# OBCv4_20.net
KiCad netlist of a schematic drawn in EAGLE
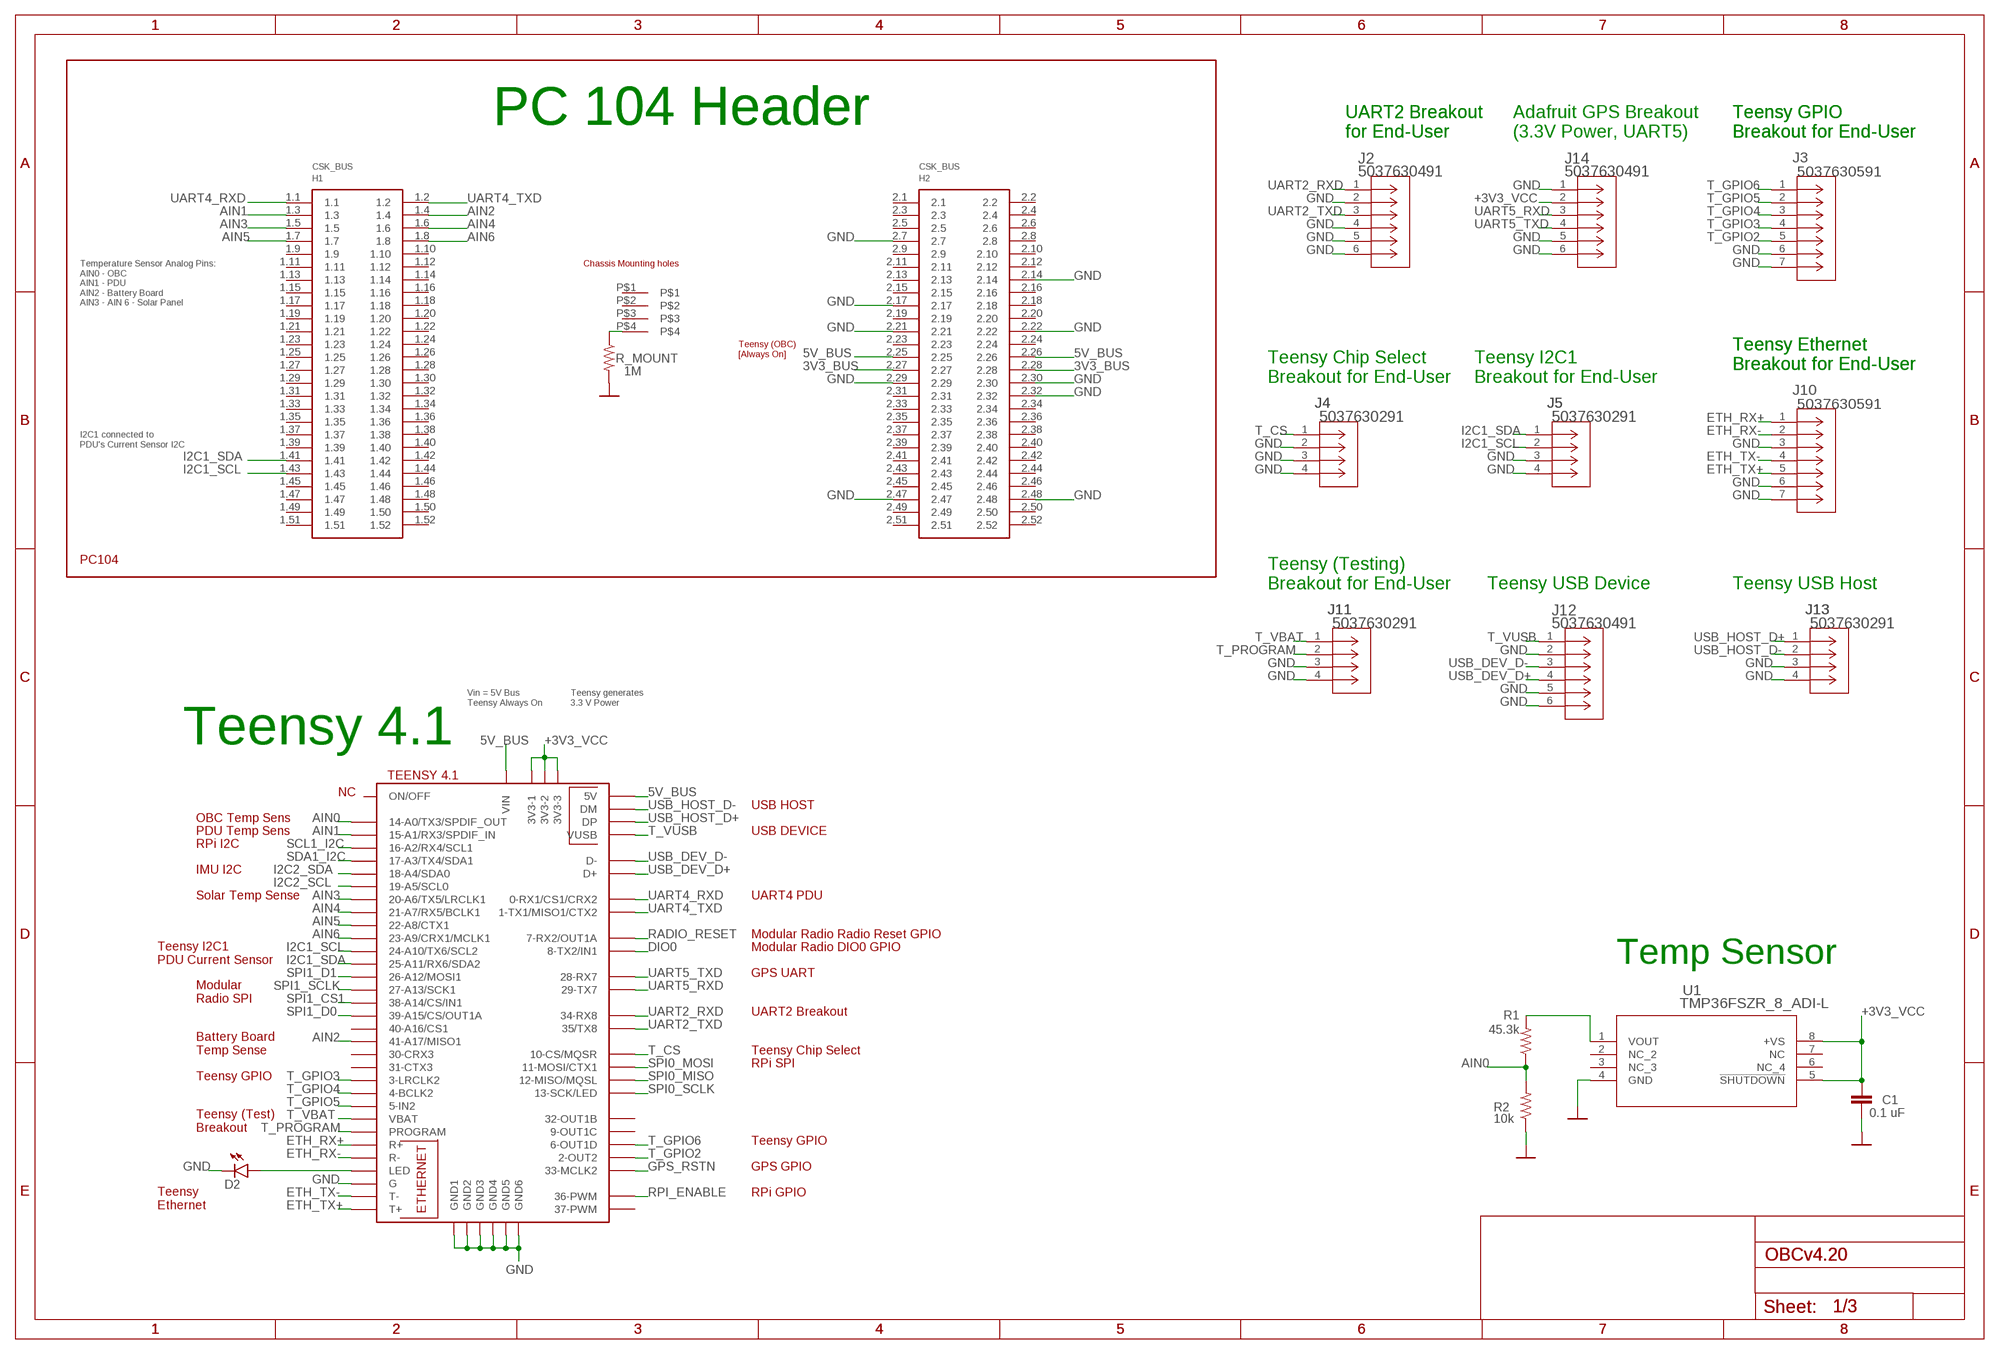
[diagram p0: schematic, sheet 1]
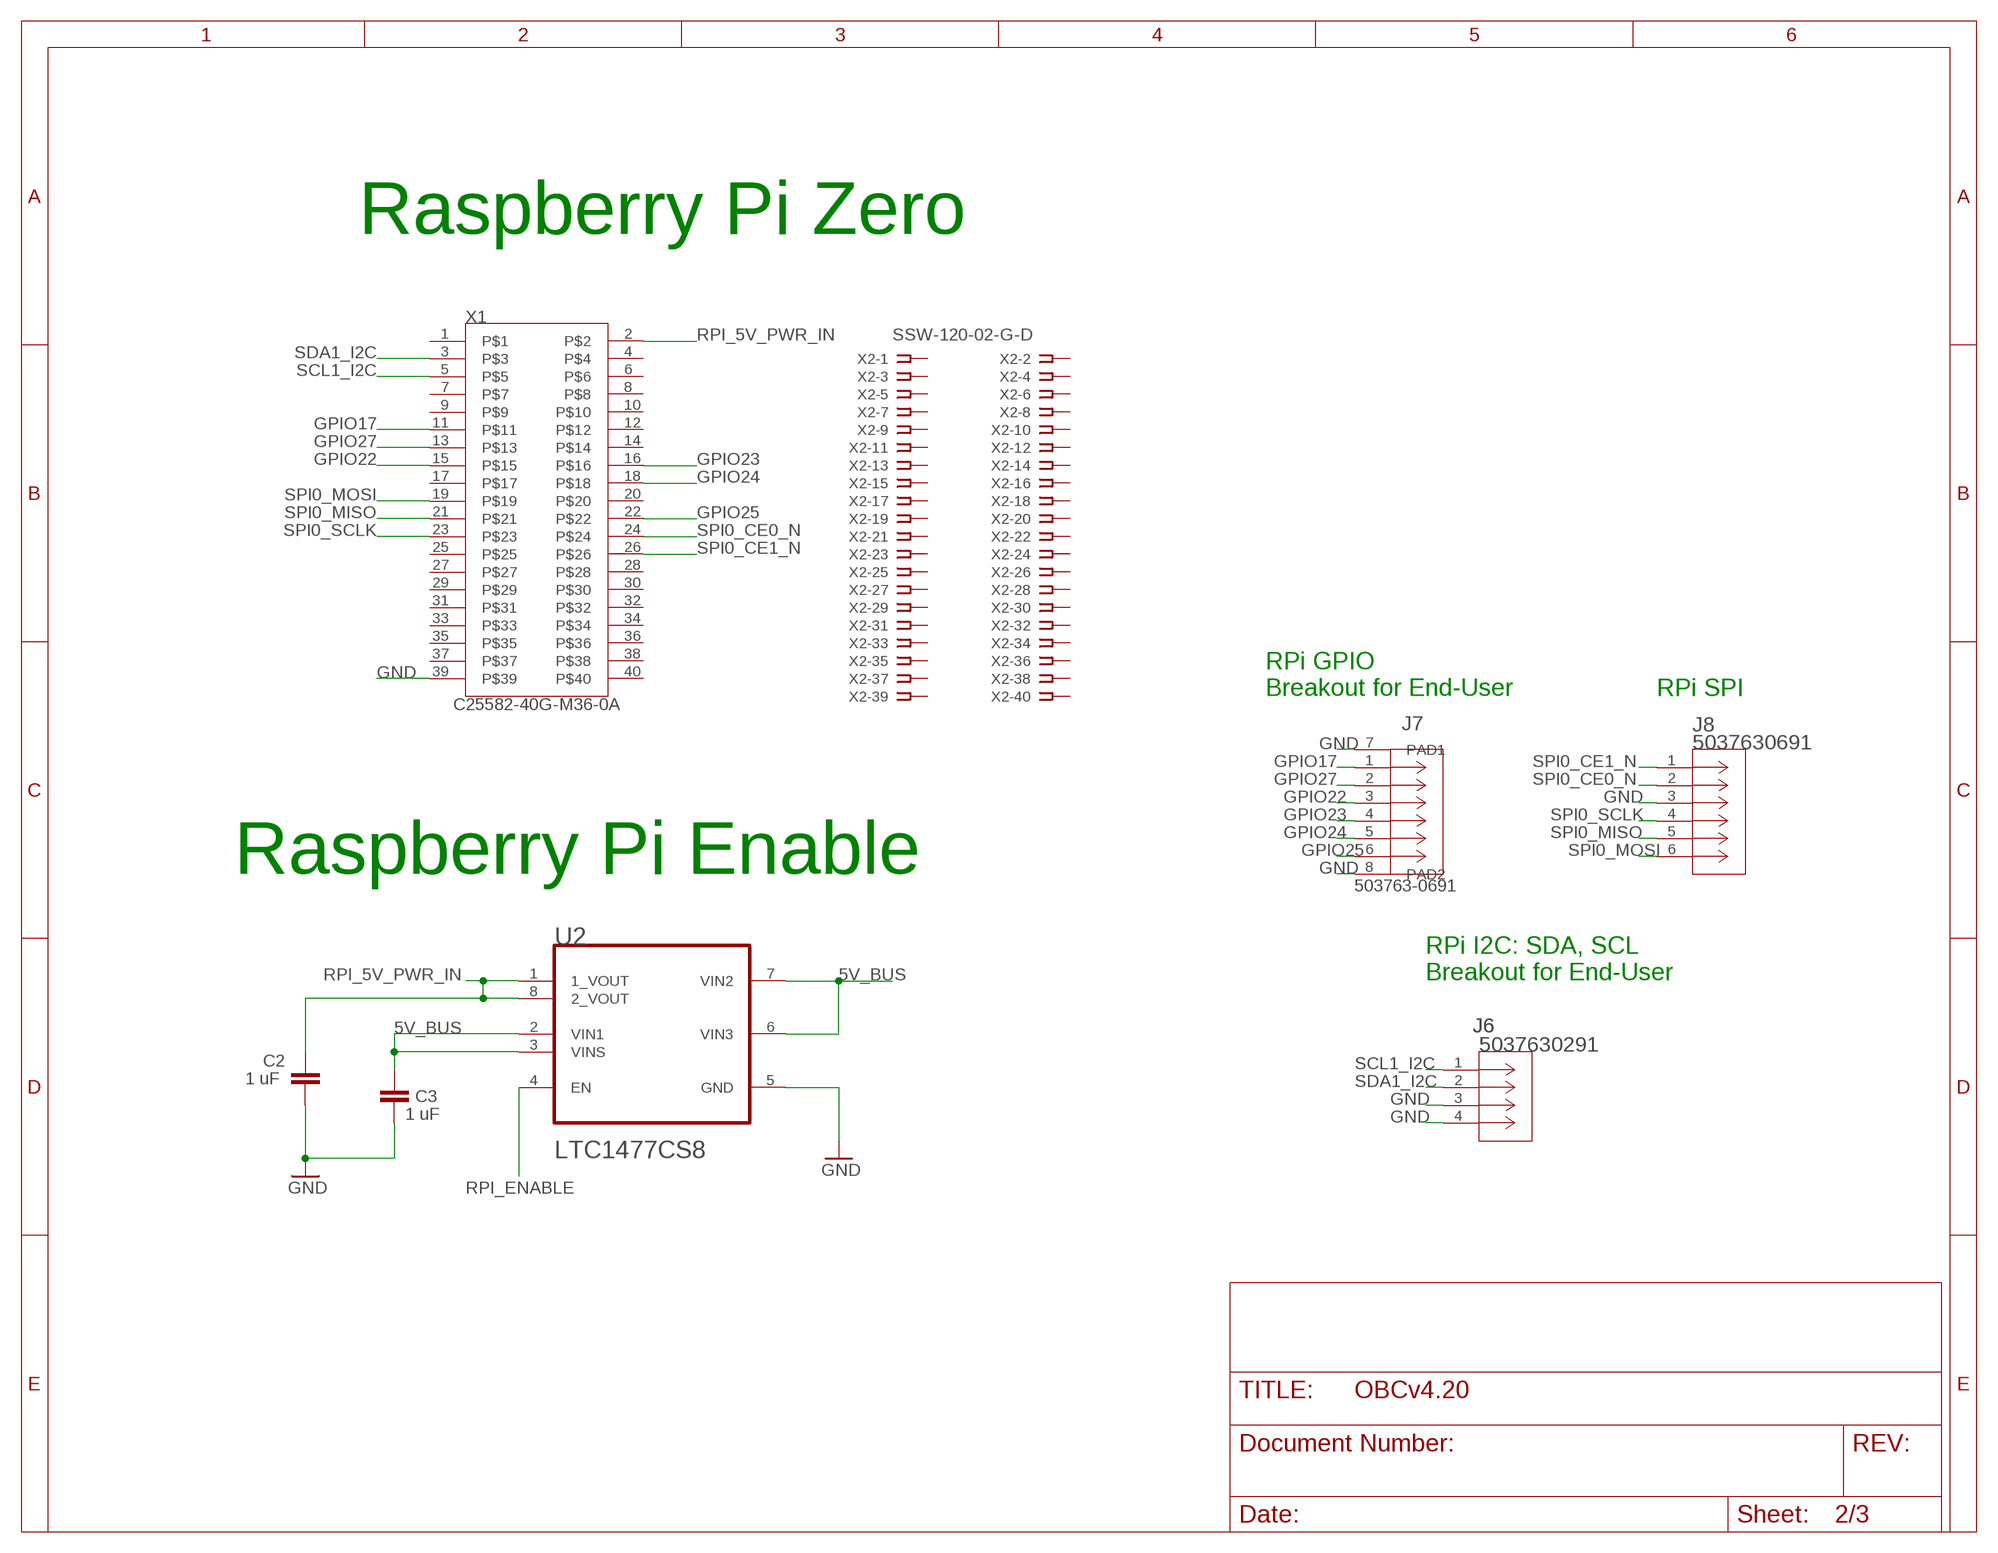
[diagram p1: schematic, sheet 2]
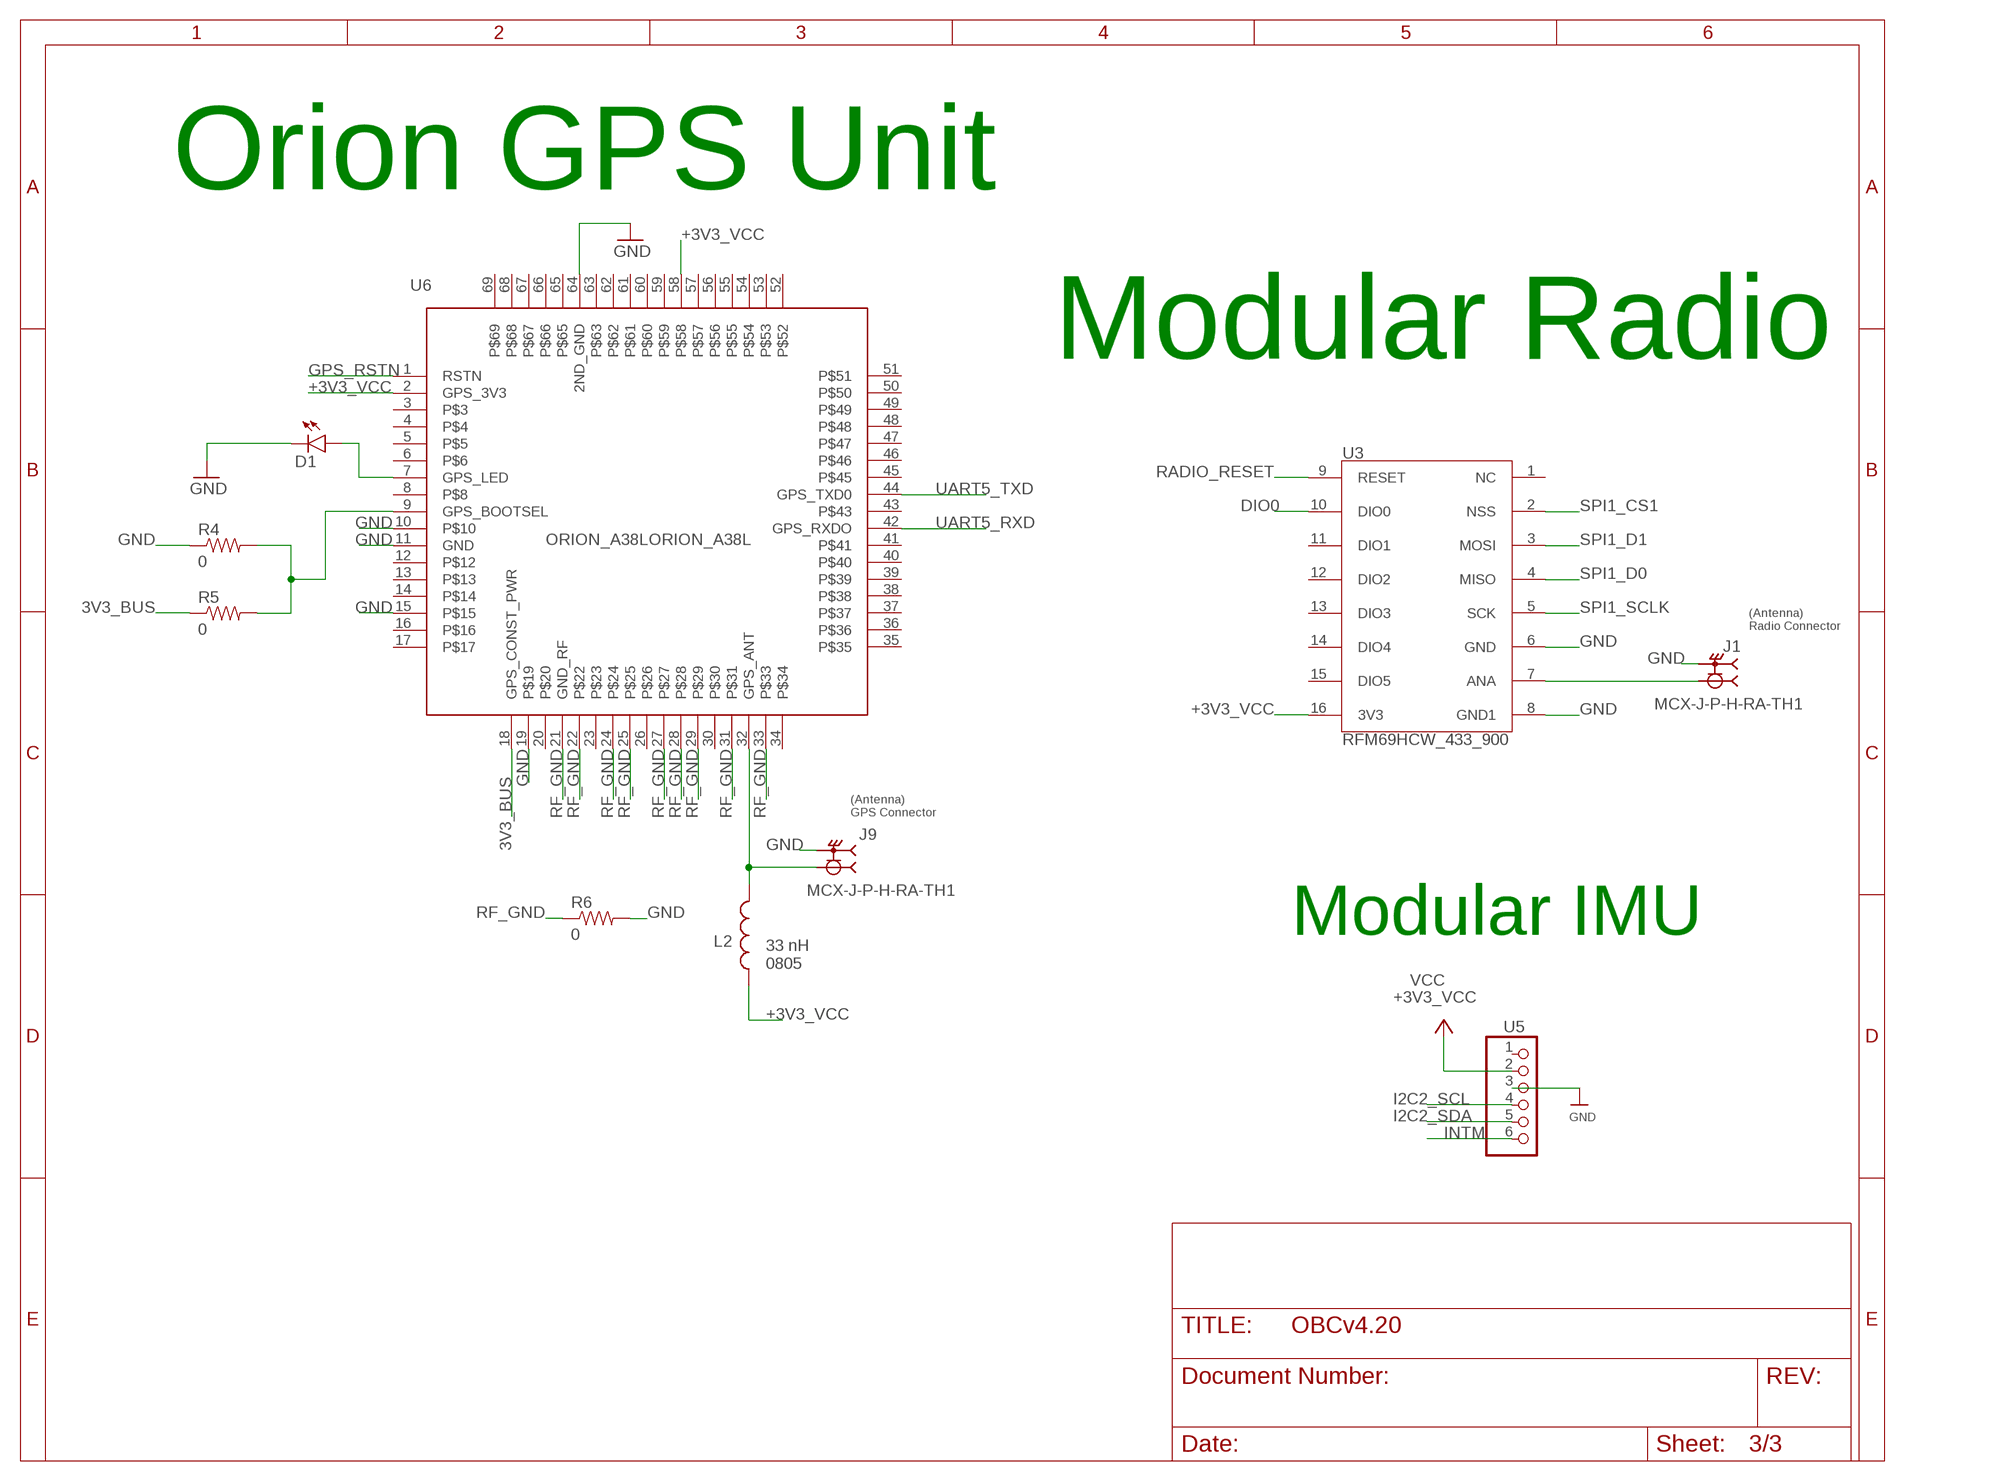
[diagram p2: schematic, sheet 3]

(export (version "E")
  (design (tool "Eeschema 10.0.6"))
  (components
    (comp (ref "C1")
      (value "0.1 uF")
      (footprint "eagle-import:0805")
      (libsource (lib "eagle-import") (part "CAP0805"))
    )
    (comp (ref "D2")
      (value "LEDCHIP-LED0603")
      (footprint "eagle-import:CHIP-LED0603")
      (libsource (lib "eagle-import") (part "LEDCHIP-LED0603"))
    )
    (comp (ref "H1")
      (value "PC104_WCONN")
      (footprint "eagle-import:PC104_WCONN")
      (libsource (lib "eagle-import") (part "PC104_WCONN"))
    )
    (comp (ref "J2")
      (value "5037630491")
      (footprint "eagle-import:CON_5037630491")
      (fields (field (name "COPYRIGHT") "Copyright (C) 2018 Accelerated Designs. All rights reserved"))
      (libsource (lib "eagle-import") (part "5037630491"))
    )
    (comp (ref "J3")
      (value "5037630591")
      (footprint "eagle-import:CON_5037630591")
      (fields (field (name "COPYRIGHT") "Copyright (C) 2021 Ultra Librarian. All rights reserved."))
      (libsource (lib "eagle-import") (part "5037630591"))
    )
    (comp (ref "J4")
      (value "5037630291")
      (footprint "eagle-import:CON_5037630291")
      (fields (field (name "COPYRIGHT") "Copyright (C) 2018 Accelerated Designs. All rights reserved"))
      (libsource (lib "eagle-import") (part "5037630291"))
    )
    (comp (ref "J5")
      (value "5037630291")
      (footprint "eagle-import:CON_5037630291")
      (fields (field (name "COPYRIGHT") "Copyright (C) 2018 Accelerated Designs. All rights reserved"))
      (libsource (lib "eagle-import") (part "5037630291"))
    )
    (comp (ref "J10")
      (value "5037630591")
      (footprint "eagle-import:CON_5037630591")
      (fields (field (name "COPYRIGHT") "Copyright (C) 2021 Ultra Librarian. All rights reserved."))
      (libsource (lib "eagle-import") (part "5037630591"))
    )
    (comp (ref "J11")
      (value "5037630291")
      (footprint "eagle-import:CON_5037630291")
      (fields (field (name "COPYRIGHT") "Copyright (C) 2018 Accelerated Designs. All rights reserved"))
      (libsource (lib "eagle-import") (part "5037630291"))
    )
    (comp (ref "J12")
      (value "5037630491")
      (footprint "eagle-import:CON_5037630491")
      (fields (field (name "COPYRIGHT") "Copyright (C) 2018 Accelerated Designs. All rights reserved"))
      (libsource (lib "eagle-import") (part "5037630491"))
    )
    (comp (ref "J13")
      (value "5037630291")
      (footprint "eagle-import:CON_5037630291")
      (fields (field (name "COPYRIGHT") "Copyright (C) 2018 Accelerated Designs. All rights reserved"))
      (libsource (lib "eagle-import") (part "5037630291"))
    )
    (comp (ref "J14")
      (value "5037630491")
      (footprint "eagle-import:CON_5037630491")
      (fields (field (name "COPYRIGHT") "Copyright (C) 2018 Accelerated Designs. All rights reserved"))
      (libsource (lib "eagle-import") (part "5037630491"))
    )
    (comp (ref "R1")
      (value "45.3k")
      (footprint "eagle-import:0805")
      (libsource (lib "eagle-import") (part "RESISTOR0805-RES"))
    )
    (comp (ref "R2")
      (value "10k")
      (footprint "eagle-import:0805")
      (libsource (lib "eagle-import") (part "RESISTOR0805-RES"))
    )
    (comp (ref "R_MOUNT")
      (value "1M")
      (footprint "eagle-import:0805")
      (libsource (lib "eagle-import") (part "RESISTOR0805-RES"))
    )
    (comp (ref "U$1")
      (value "TEENSY41")
      (footprint "eagle-import:TEENSY41")
      (libsource (lib "eagle-import") (part "TEENSY41"))
    )
    (comp (ref "U1")
      (value "TMP36FSZR_8_ADI-L")
      (footprint "eagle-import:R_8_ADI-L")
      (fields
        (field (name "MANUFACTURER_PART_NUMBER") "TMP36FSZ")
        (field (name "COPYRIGHT") "Copyright (C) 2021 Ultra Librarian. All rights reserved.")
      )
      (libsource (lib "eagle-import") (part "TMP36FSZR_8_ADI-L"))
    )
    (comp (ref "D1")
      (value "LEDCHIP-LED0603")
      (footprint "eagle-import:CHIP-LED0603")
      (libsource (lib "eagle-import") (part "LEDCHIP-LED0603"))
    )
    (comp (ref "J1")
      (value "MCX-J-P-H-RA-TH1")
      (footprint "eagle-import:SAMTEC_MCX-J-P-H-RA-TH1")
      (fields (field (name "DIGI-KEY_PART_NUMBER") "SAM10607-ND") (field (name "MF") "Samtec"))
      (libsource (lib "eagle-import") (part "MCX-J-P-H-RA-TH1"))
    )
    (comp (ref "J9")
      (value "MCX-J-P-H-RA-TH1")
      (footprint "eagle-import:SAMTEC_MCX-J-P-H-RA-TH1")
      (fields (field (name "DIGI-KEY_PART_NUMBER") "SAM10607-ND") (field (name "MF") "Samtec"))
      (libsource (lib "eagle-import") (part "MCX-J-P-H-RA-TH1"))
    )
    (comp (ref "L2")
      (value "AIMC-0805-2N2S-T")
      (footprint "eagle-import:INDC2012X105N")
      (fields (field (name "DIGI-KEY_PART_NUMBER") "535-11562-1-ND") (field (name "MF") "Abracon"))
      (libsource (lib "eagle-import") (part "AIMC-0805-2N2S-T"))
    )
    (comp (ref "R4")
      (value "0")
      (footprint "eagle-import:0805")
      (libsource (lib "eagle-import") (part "RESISTOR0805-RES"))
    )
    (comp (ref "R5")
      (value "0")
      (footprint "eagle-import:0805")
      (libsource (lib "eagle-import") (part "RESISTOR0805-RES"))
    )
    (comp (ref "R6")
      (value "0")
      (footprint "eagle-import:0805")
      (libsource (lib "eagle-import") (part "RESISTOR0805-RES"))
    )
    (comp (ref "U3")
      (value "RFM69HCW_433_900")
      (footprint "eagle-import:RFM69HCW_433")
      (libsource (lib "eagle-import") (part "RFM69HCW_433_900"))
    )
    (comp (ref "U5")
      (value "HEADER-1X670MIL")
      (footprint "eagle-import:1X06_ROUND_70")
      (libsource (lib "eagle-import") (part "HEADER-1X670MIL"))
    )
    (comp (ref "U6")
      (value "ORION_A38LORION_A38L")
      (footprint "eagle-import:ORION_A38L")
      (libsource (lib "eagle-import") (part "ORION_A38LORION_A38L"))
    )
    (comp (ref "C2")
      (value "1 uF")
      (footprint "eagle-import:0805")
      (libsource (lib "eagle-import") (part "CAP0805"))
    )
    (comp (ref "C3")
      (value "1 uF")
      (footprint "eagle-import:0805")
      (libsource (lib "eagle-import") (part "CAP0805"))
    )
    (comp (ref "J6")
      (value "5037630291")
      (footprint "eagle-import:CON_5037630291")
      (fields (field (name "COPYRIGHT") "Copyright (C) 2018 Accelerated Designs. All rights reserved"))
      (libsource (lib "eagle-import") (part "5037630291"))
    )
    (comp (ref "J7")
      (value "503763-0691")
      (footprint "eagle-import:CONN_503763-0691_MOL")
      (fields (field (name "COPYRIGHT") "Copyright (C) 2018 Accelerated Designs. All rights reserved"))
      (libsource (lib "eagle-import") (part "503763-0691"))
    )
    (comp (ref "J8")
      (value "5037630691")
      (footprint "eagle-import:CONN_503763-0691_MOL")
      (fields
        (field (name "MANUFACTURER_PART_NUMBER") "503763-0691")
        (field (name "COPYRIGHT") "Copyright (C) 2018 Accelerated Designs. All rights reserved")
      )
      (libsource (lib "eagle-import") (part "5037630691"))
    )
    (comp (ref "U2")
      (value "LTC1477CS8LINEAR_TECHNOLOGY_LTC1477CS8_0_2")
      (footprint "eagle-import:LINEAR_TECHNOLOGY_LTC1477CS8_2")
      (fields (field (name "MF") "Linear Technology") (field (name "MPN") "LTC1477CS8"))
      (libsource (lib "eagle-import") (part "LTC1477CS8LINEAR_TECHNOLOGY_LTC1477CS8_0_2"))
    )
    (comp (ref "X1")
      (value "C25582-40G-M36-0A")
      (footprint "eagle-import:ADAFRUIT_C25582-40G-M36-0A_0")
      (libsource (lib "eagle-import") (part "C25582-40G-M36-0A"))
    )
    (comp (ref "X2")
      (value "SSW-120-02-G-D")
      (footprint "eagle-import:SSW-120-02-G-D")
      (fields (field (name "MF") "Samtec Inc."))
      (libsource (lib "eagle-import") (part "SSW-120-02-G-D"))
    )
  )
  (nets
    (net (code "1") (name "+3V3_VCC") (class "Default")
      (node (ref "C1") (pin "1") (pinfunction "1_1") (pintype "passive"))
      (node (ref "J14") (pin "2") (pinfunction "2_2") (pintype "passive"))
      (node (ref "L2") (pin "1") (pinfunction "1_1") (pintype "passive"))
      (node (ref "U$1") (pin "3V3-1") (pinfunction "3V3-1_3V3-1") (pintype "bidirectional"))
      (node (ref "U$1") (pin "3V3-2") (pinfunction "3V3-2_3V3-2") (pintype "bidirectional"))
      (node (ref "U$1") (pin "3V3-3") (pinfunction "3V3-3_3V3-3") (pintype "bidirectional"))
      (node (ref "U1") (pin "5") (pinfunction "~{SHUTDOWN}_5") (pintype "passive"))
      (node (ref "U1") (pin "8") (pinfunction "+VS_8") (pintype "power_in"))
      (node (ref "U3") (pin "16") (pinfunction "3V3_16") (pintype "bidirectional"))
      (node (ref "U5") (pin "2") (pinfunction "2_2") (pintype "passive"))
      (node (ref "U6") (pin "2") (pinfunction "GPS_3V3_2") (pintype "bidirectional"))
      (node (ref "U6") (pin "58") (pinfunction "P$58_58") (pintype "bidirectional"))
    )
    (net (code "2") (name "3V3_BUS") (class "Default")
      (node (ref "H1") (pin "2.27") (pinfunction "2.27_2.27") (pintype "bidirectional"))
      (node (ref "H1") (pin "2.28") (pinfunction "2.28_2.28") (pintype "bidirectional"))
      (node (ref "R5") (pin "1") (pinfunction "1_1") (pintype "passive"))
      (node (ref "U6") (pin "18") (pinfunction "GPS_CONST_PWR_18") (pintype "bidirectional"))
    )
    (net (code "3") (name "5V_BUS") (class "Default")
      (node (ref "C3") (pin "1") (pinfunction "1_1") (pintype "passive"))
      (node (ref "H1") (pin "2.25") (pinfunction "2.25_2.25") (pintype "bidirectional"))
      (node (ref "H1") (pin "2.26") (pinfunction "2.26_2.26") (pintype "bidirectional"))
      (node (ref "U$1") (pin "+5V") (pinfunction "5V_+5V") (pintype "bidirectional"))
      (node (ref "U$1") (pin "VIN") (pinfunction "VIN_VIN") (pintype "bidirectional"))
      (node (ref "U2") (pin "2") (pinfunction "VIN1_2") (pintype "power_in"))
      (node (ref "U2") (pin "3") (pinfunction "VINS_3") (pintype "power_in"))
      (node (ref "U2") (pin "6") (pinfunction "VIN3_6") (pintype "power_in"))
      (node (ref "U2") (pin "7") (pinfunction "VIN2_7") (pintype "power_in"))
    )
    (net (code "4") (name "AIN0") (class "Default")
      (node (ref "R1") (pin "1") (pinfunction "1_1") (pintype "passive"))
      (node (ref "R2") (pin "2") (pinfunction "2_2") (pintype "passive"))
      (node (ref "U$1") (pin "14-A0/TX3/SPDIF_OUT") (pinfunction "14-A0/TX3/SPDIF_OUT_14-A0/TX3/SPDIF_OUT") (pintype "bidirectional"))
    )
    (net (code "5") (name "AIN1") (class "Default")
      (node (ref "H1") (pin "1.3") (pinfunction "1.3_1.3") (pintype "bidirectional"))
      (node (ref "U$1") (pin "15-A1/RX3/SPDIF_IN") (pinfunction "15-A1/RX3/SPDIF_IN_15-A1/RX3/SPDIF_IN") (pintype "bidirectional"))
    )
    (net (code "6") (name "AIN2") (class "Default")
      (node (ref "H1") (pin "1.4") (pinfunction "1.4_1.4") (pintype "bidirectional"))
      (node (ref "U$1") (pin "41-A17/MISO1") (pinfunction "41-A17/MISO1_41-A17/MISO1") (pintype "bidirectional"))
    )
    (net (code "7") (name "AIN3") (class "Default")
      (node (ref "H1") (pin "1.5") (pinfunction "1.5_1.5") (pintype "bidirectional"))
      (node (ref "U$1") (pin "20-A6/TX5/LRCLK1") (pinfunction "20-A6/TX5/LRCLK1_20-A6/TX5/LRCLK1") (pintype "bidirectional"))
    )
    (net (code "8") (name "AIN4") (class "Default")
      (node (ref "H1") (pin "1.6") (pinfunction "1.6_1.6") (pintype "bidirectional"))
      (node (ref "U$1") (pin "21-A7/RX5/BCLK1") (pinfunction "21-A7/RX5/BCLK1_21-A7/RX5/BCLK1") (pintype "bidirectional"))
    )
    (net (code "9") (name "AIN5") (class "Default")
      (node (ref "H1") (pin "1.7") (pinfunction "1.7_1.7") (pintype "bidirectional"))
      (node (ref "U$1") (pin "22-A8/CTX1") (pinfunction "22-A8/CTX1_22-A8/CTX1") (pintype "bidirectional"))
    )
    (net (code "10") (name "AIN6") (class "Default")
      (node (ref "H1") (pin "1.8") (pinfunction "1.8_1.8") (pintype "bidirectional"))
      (node (ref "U$1") (pin "23-A9/CRX1/MCLK1") (pinfunction "23-A9/CRX1/MCLK1_23-A9/CRX1/MCLK1") (pintype "bidirectional"))
    )
    (net (code "11") (name "DIO0") (class "Default")
      (node (ref "U$1") (pin "8-TX2/IN1") (pinfunction "8-TX2/IN1_8-TX2/IN1") (pintype "bidirectional"))
      (node (ref "U3") (pin "10") (pinfunction "DIO0_10") (pintype "bidirectional"))
    )
    (net (code "12") (name "ETH_RX+") (class "Default")
      (node (ref "J10") (pin "1") (pinfunction "1_1") (pintype "passive"))
      (node (ref "U$1") (pin "R+") (pinfunction "R+_R+") (pintype "bidirectional"))
    )
    (net (code "13") (name "ETH_RX-") (class "Default")
      (node (ref "J10") (pin "2") (pinfunction "2_2") (pintype "passive"))
      (node (ref "U$1") (pin "R-") (pinfunction "R-_R-") (pintype "bidirectional"))
    )
    (net (code "14") (name "ETH_TX+") (class "Default")
      (node (ref "J10") (pin "5") (pinfunction "5_5") (pintype "passive"))
      (node (ref "U$1") (pin "T+") (pinfunction "T+_T+") (pintype "bidirectional"))
    )
    (net (code "15") (name "ETH_TX-") (class "Default")
      (node (ref "J10") (pin "4") (pinfunction "4_4") (pintype "passive"))
      (node (ref "U$1") (pin "T-") (pinfunction "T-_T-") (pintype "bidirectional"))
    )
    (net (code "16") (name "GND") (class "Default")
      (node (ref "C1") (pin "2") (pinfunction "2_2") (pintype "passive"))
      (node (ref "C2") (pin "2") (pinfunction "2_2") (pintype "passive"))
      (node (ref "C3") (pin "2") (pinfunction "2_2") (pintype "passive"))
      (node (ref "D1") (pin "C") (pinfunction "C_C") (pintype "passive"))
      (node (ref "D2") (pin "C") (pinfunction "C_C") (pintype "passive"))
      (node (ref "H1") (pin "2.14") (pinfunction "2.14_2.14") (pintype "bidirectional"))
      (node (ref "H1") (pin "2.17") (pinfunction "2.17_2.17") (pintype "bidirectional"))
      (node (ref "H1") (pin "2.21") (pinfunction "2.21_2.21") (pintype "bidirectional"))
      (node (ref "H1") (pin "2.22") (pinfunction "2.22_2.22") (pintype "bidirectional"))
      (node (ref "H1") (pin "2.29") (pinfunction "2.29_2.29") (pintype "bidirectional"))
      (node (ref "H1") (pin "2.30") (pinfunction "2.30_2.30") (pintype "bidirectional"))
      (node (ref "H1") (pin "2.32") (pinfunction "2.32_2.32") (pintype "bidirectional"))
      (node (ref "H1") (pin "2.47") (pinfunction "2.47_2.47") (pintype "bidirectional"))
      (node (ref "H1") (pin "2.48") (pinfunction "2.48_2.48") (pintype "bidirectional"))
      (node (ref "H1") (pin "2.7") (pinfunction "2.7_2.7") (pintype "bidirectional"))
      (node (ref "J1") (pin "S1") (pinfunction "2_S1") (pintype "passive"))
      (node (ref "J1") (pin "S2") (pinfunction "2_S2") (pintype "passive"))
      (node (ref "J1") (pin "S3") (pinfunction "2_S3") (pintype "passive"))
      (node (ref "J1") (pin "S4") (pinfunction "2_S4") (pintype "passive"))
      (node (ref "J10") (pin "3") (pinfunction "3_3") (pintype "passive"))
      (node (ref "J10") (pin "6") (pinfunction "6_6") (pintype "passive"))
      (node (ref "J10") (pin "7") (pinfunction "7_7") (pintype "passive"))
      (node (ref "J11") (pin "3") (pinfunction "3_3") (pintype "passive"))
      (node (ref "J11") (pin "4") (pinfunction "4_4") (pintype "passive"))
      (node (ref "J12") (pin "2") (pinfunction "2_2") (pintype "passive"))
      (node (ref "J12") (pin "5") (pinfunction "5_5") (pintype "passive"))
      (node (ref "J12") (pin "6") (pinfunction "6_6") (pintype "passive"))
      (node (ref "J13") (pin "3") (pinfunction "3_3") (pintype "passive"))
      (node (ref "J13") (pin "4") (pinfunction "4_4") (pintype "passive"))
      (node (ref "J14") (pin "1") (pinfunction "1_1") (pintype "passive"))
      (node (ref "J14") (pin "5") (pinfunction "5_5") (pintype "passive"))
      (node (ref "J14") (pin "6") (pinfunction "6_6") (pintype "passive"))
      (node (ref "J2") (pin "2") (pinfunction "2_2") (pintype "passive"))
      (node (ref "J2") (pin "4") (pinfunction "4_4") (pintype "passive"))
      (node (ref "J2") (pin "5") (pinfunction "5_5") (pintype "passive"))
      (node (ref "J2") (pin "6") (pinfunction "6_6") (pintype "passive"))
      (node (ref "J3") (pin "6") (pinfunction "6_6") (pintype "passive"))
      (node (ref "J3") (pin "7") (pinfunction "7_7") (pintype "passive"))
      (node (ref "J4") (pin "2") (pinfunction "2_2") (pintype "passive"))
      (node (ref "J4") (pin "3") (pinfunction "3_3") (pintype "passive"))
      (node (ref "J4") (pin "4") (pinfunction "4_4") (pintype "passive"))
      (node (ref "J5") (pin "3") (pinfunction "3_3") (pintype "passive"))
      (node (ref "J5") (pin "4") (pinfunction "4_4") (pintype "passive"))
      (node (ref "J6") (pin "3") (pinfunction "3_3") (pintype "passive"))
      (node (ref "J6") (pin "4") (pinfunction "4_4") (pintype "passive"))
      (node (ref "J7") (pin "7") (pinfunction "PAD1_7") (pintype "bidirectional"))
      (node (ref "J7") (pin "8") (pinfunction "PAD2_8") (pintype "bidirectional"))
      (node (ref "J8") (pin "3") (pinfunction "3_3") (pintype "passive"))
      (node (ref "J9") (pin "S1") (pinfunction "2_S1") (pintype "passive"))
      (node (ref "J9") (pin "S2") (pinfunction "2_S2") (pintype "passive"))
      (node (ref "J9") (pin "S3") (pinfunction "2_S3") (pintype "passive"))
      (node (ref "J9") (pin "S4") (pinfunction "2_S4") (pintype "passive"))
      (node (ref "R2") (pin "1") (pinfunction "1_1") (pintype "passive"))
      (node (ref "R4") (pin "1") (pinfunction "1_1") (pintype "passive"))
      (node (ref "R6") (pin "2") (pinfunction "2_2") (pintype "passive"))
      (node (ref "R_MOUNT") (pin "2") (pinfunction "2_2") (pintype "passive"))
      (node (ref "U$1") (pin "G") (pinfunction "G_G") (pintype "bidirectional"))
      (node (ref "U$1") (pin "GND1") (pinfunction "GND1_GND1") (pintype "bidirectional"))
      (node (ref "U$1") (pin "GND2") (pinfunction "GND2_GND2") (pintype "bidirectional"))
      (node (ref "U$1") (pin "GND3") (pinfunction "GND3_GND3") (pintype "bidirectional"))
      (node (ref "U$1") (pin "GND4") (pinfunction "GND4_GND4") (pintype "bidirectional"))
      (node (ref "U$1") (pin "GND5") (pinfunction "GND5_GND5") (pintype "bidirectional"))
      (node (ref "U$1") (pin "GND6") (pinfunction "GND6_GND6") (pintype "bidirectional"))
      (node (ref "U1") (pin "4") (pinfunction "GND_4") (pintype "passive"))
      (node (ref "U2") (pin "5") (pinfunction "GND_5") (pintype "power_in"))
      (node (ref "U3") (pin "6") (pinfunction "GND_6") (pintype "bidirectional"))
      (node (ref "U3") (pin "8") (pinfunction "GND1_8") (pintype "bidirectional"))
      (node (ref "U5") (pin "3") (pinfunction "3_3") (pintype "passive"))
      (node (ref "U6") (pin "10") (pinfunction "P$10_10") (pintype "bidirectional"))
      (node (ref "U6") (pin "11") (pinfunction "GND_11") (pintype "bidirectional"))
      (node (ref "U6") (pin "15") (pinfunction "P$15_15") (pintype "bidirectional"))
      (node (ref "U6") (pin "19") (pinfunction "P$19_19") (pintype "bidirectional"))
      (node (ref "U6") (pin "64") (pinfunction "2ND_GND_64") (pintype "bidirectional"))
      (node (ref "X1") (pin "39") (pinfunction "P$39_39") (pintype "bidirectional"))
    )
    (net (code "17") (name "GPIO17") (class "Default")
      (node (ref "J7") (pin "1") (pinfunction "1_1") (pintype "passive"))
      (node (ref "X1") (pin "11") (pinfunction "P$11_11") (pintype "bidirectional"))
    )
    (net (code "18") (name "GPIO22") (class "Default")
      (node (ref "J7") (pin "3") (pinfunction "3_3") (pintype "passive"))
      (node (ref "X1") (pin "15") (pinfunction "P$15_15") (pintype "bidirectional"))
    )
    (net (code "19") (name "GPIO23") (class "Default")
      (node (ref "J7") (pin "4") (pinfunction "4_4") (pintype "passive"))
      (node (ref "X1") (pin "16") (pinfunction "P$16_16") (pintype "bidirectional"))
    )
    (net (code "20") (name "GPIO24") (class "Default")
      (node (ref "J7") (pin "5") (pinfunction "5_5") (pintype "passive"))
      (node (ref "X1") (pin "18") (pinfunction "P$18_18") (pintype "bidirectional"))
    )
    (net (code "21") (name "GPIO25") (class "Default")
      (node (ref "J7") (pin "6") (pinfunction "6_6") (pintype "passive"))
      (node (ref "X1") (pin "22") (pinfunction "P$22_22") (pintype "bidirectional"))
    )
    (net (code "22") (name "GPIO27") (class "Default")
      (node (ref "J7") (pin "2") (pinfunction "2_2") (pintype "passive"))
      (node (ref "X1") (pin "13") (pinfunction "P$13_13") (pintype "bidirectional"))
    )
    (net (code "23") (name "GPS_RSTN") (class "Default")
      (node (ref "U$1") (pin "33-MCLK2") (pinfunction "33-MCLK2_33-MCLK2") (pintype "bidirectional"))
      (node (ref "U6") (pin "1") (pinfunction "RSTN_1") (pintype "bidirectional"))
    )
    (net (code "24") (name "I2C1_SCL") (class "Default")
      (node (ref "H1") (pin "1.43") (pinfunction "1.43_1.43") (pintype "bidirectional"))
      (node (ref "J5") (pin "2") (pinfunction "2_2") (pintype "passive"))
      (node (ref "U$1") (pin "24-A10/TX6/SCL2") (pinfunction "24-A10/TX6/SCL2_24-A10/TX6/SCL2") (pintype "bidirectional"))
    )
    (net (code "25") (name "I2C1_SDA") (class "Default")
      (node (ref "H1") (pin "1.41") (pinfunction "1.41_1.41") (pintype "bidirectional"))
      (node (ref "J5") (pin "1") (pinfunction "1_1") (pintype "passive"))
      (node (ref "U$1") (pin "25-A11/RX6/SDA2") (pinfunction "25-A11/RX6/SDA2_25-A11/RX6/SDA2") (pintype "bidirectional"))
    )
    (net (code "26") (name "I2C2_SCL") (class "Default")
      (node (ref "U$1") (pin "19-A5/SCL0") (pinfunction "19-A5/SCL0_19-A5/SCL0") (pintype "bidirectional"))
      (node (ref "U5") (pin "4") (pinfunction "4_4") (pintype "passive"))
    )
    (net (code "27") (name "I2C2_SDA") (class "Default")
      (node (ref "U$1") (pin "18-A4/SDA0") (pinfunction "18-A4/SDA0_18-A4/SDA0") (pintype "bidirectional"))
      (node (ref "U5") (pin "5") (pinfunction "5_5") (pintype "passive"))
    )
    (net (code "28") (name "INTM") (class "Default")
      (node (ref "U5") (pin "6") (pinfunction "6_6") (pintype "passive"))
    )
    (net (code "29") (name "Net-(D2-PadA)") (class "Default")
      (node (ref "D2") (pin "A") (pinfunction "A_A") (pintype "passive"))
      (node (ref "U$1") (pin "LED") (pinfunction "LED_LED") (pintype "bidirectional"))
    )
    (net (code "30") (name "Net-(H1-PadP$4)") (class "Default")
      (node (ref "H1") (pin "P$4") (pinfunction "P$4_P$4") (pintype "bidirectional"))
      (node (ref "R_MOUNT") (pin "1") (pinfunction "1_1") (pintype "passive"))
    )
    (net (code "31") (name "Net-(U1-VOUT)") (class "Default")
      (node (ref "R1") (pin "2") (pinfunction "2_2") (pintype "passive"))
      (node (ref "U1") (pin "1") (pinfunction "VOUT_1") (pintype "output"))
    )
    (net (code "32") (name "Net-(U3-ANA)") (class "Default")
      (node (ref "J1") (pin "1") (pinfunction "1_1") (pintype "passive"))
      (node (ref "U3") (pin "7") (pinfunction "ANA_7") (pintype "bidirectional"))
    )
    (net (code "33") (name "Net-(U6-GPS_ANT)") (class "Default")
      (node (ref "J9") (pin "1") (pinfunction "1_1") (pintype "passive"))
      (node (ref "L2") (pin "2") (pinfunction "2_2") (pintype "passive"))
      (node (ref "U6") (pin "32") (pinfunction "GPS_ANT_32") (pintype "bidirectional"))
    )
    (net (code "34") (name "Net-(U6-GPS_BOOTSEL)") (class "Default")
      (node (ref "R4") (pin "2") (pinfunction "2_2") (pintype "passive"))
      (node (ref "R5") (pin "2") (pinfunction "2_2") (pintype "passive"))
      (node (ref "U6") (pin "9") (pinfunction "GPS_BOOTSEL_9") (pintype "bidirectional"))
    )
    (net (code "35") (name "Net-(U6-GPS_LED)") (class "Default")
      (node (ref "D1") (pin "A") (pinfunction "A_A") (pintype "passive"))
      (node (ref "U6") (pin "7") (pinfunction "GPS_LED_7") (pintype "bidirectional"))
    )
    (net (code "36") (name "RADIO_RESET") (class "Default")
      (node (ref "U$1") (pin "7-RX2/OUT1A") (pinfunction "7-RX2/OUT1A_7-RX2/OUT1A") (pintype "bidirectional"))
      (node (ref "U3") (pin "9") (pinfunction "RESET_9") (pintype "bidirectional"))
    )
    (net (code "37") (name "RF_GND") (class "Default")
      (node (ref "R6") (pin "1") (pinfunction "1_1") (pintype "passive"))
      (node (ref "U6") (pin "21") (pinfunction "GND_RF_21") (pintype "bidirectional"))
      (node (ref "U6") (pin "22") (pinfunction "P$22_22") (pintype "bidirectional"))
      (node (ref "U6") (pin "24") (pinfunction "P$24_24") (pintype "bidirectional"))
      (node (ref "U6") (pin "25") (pinfunction "P$25_25") (pintype "bidirectional"))
      (node (ref "U6") (pin "27") (pinfunction "P$27_27") (pintype "bidirectional"))
      (node (ref "U6") (pin "28") (pinfunction "P$28_28") (pintype "bidirectional"))
      (node (ref "U6") (pin "29") (pinfunction "P$29_29") (pintype "bidirectional"))
      (node (ref "U6") (pin "31") (pinfunction "P$31_31") (pintype "bidirectional"))
      (node (ref "U6") (pin "33") (pinfunction "P$33_33") (pintype "bidirectional"))
    )
    (net (code "38") (name "RPI_5V_PWR_IN") (class "Default")
      (node (ref "C2") (pin "1") (pinfunction "1_1") (pintype "passive"))
      (node (ref "U2") (pin "1") (pinfunction "1_VOUT_1") (pintype "power_in"))
      (node (ref "U2") (pin "8") (pinfunction "2_VOUT_8") (pintype "power_in"))
      (node (ref "X1") (pin "2") (pinfunction "P$2_2") (pintype "bidirectional"))
    )
    (net (code "39") (name "RPI_ENABLE") (class "Default")
      (node (ref "U$1") (pin "36-PWM") (pinfunction "36-PWM_36-PWM") (pintype "bidirectional"))
      (node (ref "U2") (pin "4") (pinfunction "EN_4") (pintype "input"))
    )
    (net (code "40") (name "SCL1_I2C") (class "Default")
      (node (ref "J6") (pin "1") (pinfunction "1_1") (pintype "passive"))
      (node (ref "U$1") (pin "16-A2/RX4/SCL1") (pinfunction "16-A2/RX4/SCL1_16-A2/RX4/SCL1") (pintype "bidirectional"))
      (node (ref "X1") (pin "5") (pinfunction "P$5_5") (pintype "bidirectional"))
    )
    (net (code "41") (name "SDA1_I2C") (class "Default")
      (node (ref "J6") (pin "2") (pinfunction "2_2") (pintype "passive"))
      (node (ref "U$1") (pin "17-A3/TX4/SDA1") (pinfunction "17-A3/TX4/SDA1_17-A3/TX4/SDA1") (pintype "bidirectional"))
      (node (ref "X1") (pin "3") (pinfunction "P$3_3") (pintype "bidirectional"))
    )
    (net (code "42") (name "SPI0_CE0_N") (class "Default")
      (node (ref "J8") (pin "2") (pinfunction "2_2") (pintype "passive"))
      (node (ref "X1") (pin "24") (pinfunction "P$24_24") (pintype "bidirectional"))
    )
    (net (code "43") (name "SPI0_CE1_N") (class "Default")
      (node (ref "J8") (pin "1") (pinfunction "1_1") (pintype "passive"))
      (node (ref "X1") (pin "26") (pinfunction "P$26_26") (pintype "bidirectional"))
    )
    (net (code "44") (name "SPI0_MISO") (class "Default")
      (node (ref "J8") (pin "5") (pinfunction "5_5") (pintype "passive"))
      (node (ref "U$1") (pin "12-MISO/MQSL") (pinfunction "12-MISO/MQSL_12-MISO/MQSL") (pintype "bidirectional"))
      (node (ref "X1") (pin "21") (pinfunction "P$21_21") (pintype "bidirectional"))
    )
    (net (code "45") (name "SPI0_MOSI") (class "Default")
      (node (ref "J8") (pin "6") (pinfunction "6_6") (pintype "passive"))
      (node (ref "U$1") (pin "11-MOSI/CTX1") (pinfunction "11-MOSI/CTX1_11-MOSI/CTX1") (pintype "bidirectional"))
      (node (ref "X1") (pin "19") (pinfunction "P$19_19") (pintype "bidirectional"))
    )
    (net (code "46") (name "SPI0_SCLK") (class "Default")
      (node (ref "J8") (pin "4") (pinfunction "4_4") (pintype "passive"))
      (node (ref "U$1") (pin "13-SCK/LED") (pinfunction "13-SCK/LED_13-SCK/LED") (pintype "bidirectional"))
      (node (ref "X1") (pin "23") (pinfunction "P$23_23") (pintype "bidirectional"))
    )
    (net (code "47") (name "SPI1_CS1") (class "Default")
      (node (ref "U$1") (pin "38-A14/CS/IN1") (pinfunction "38-A14/CS/IN1_38-A14/CS/IN1") (pintype "bidirectional"))
      (node (ref "U3") (pin "2") (pinfunction "NSS_2") (pintype "bidirectional"))
    )
    (net (code "48") (name "SPI1_D0") (class "Default")
      (node (ref "U$1") (pin "39-A15/CS/OUT1A") (pinfunction "39-A15/CS/OUT1A_39-A15/CS/OUT1A") (pintype "bidirectional"))
      (node (ref "U3") (pin "4") (pinfunction "MISO_4") (pintype "bidirectional"))
    )
    (net (code "49") (name "SPI1_D1") (class "Default")
      (node (ref "U$1") (pin "26-A12/MOSI1") (pinfunction "26-A12/MOSI1_26-A12/MOSI1") (pintype "bidirectional"))
      (node (ref "U3") (pin "3") (pinfunction "MOSI_3") (pintype "bidirectional"))
    )
    (net (code "50") (name "SPI1_SCLK") (class "Default")
      (node (ref "U$1") (pin "27-A13/SCK1") (pinfunction "27-A13/SCK1_27-A13/SCK1") (pintype "bidirectional"))
      (node (ref "U3") (pin "5") (pinfunction "SCK_5") (pintype "bidirectional"))
    )
    (net (code "51") (name "T_CS") (class "Default")
      (node (ref "J4") (pin "1") (pinfunction "1_1") (pintype "passive"))
      (node (ref "U$1") (pin "10-CS\\MQSR") (pinfunction "10-CS/MQSR_10-CS\\MQSR") (pintype "bidirectional"))
    )
    (net (code "52") (name "T_GPIO2") (class "Default")
      (node (ref "J3") (pin "5") (pinfunction "5_5") (pintype "passive"))
      (node (ref "U$1") (pin "2-OUT2") (pinfunction "2-OUT2_2-OUT2") (pintype "bidirectional"))
    )
    (net (code "53") (name "T_GPIO3") (class "Default")
      (node (ref "J3") (pin "4") (pinfunction "4_4") (pintype "passive"))
      (node (ref "U$1") (pin "3-LRCLK2") (pinfunction "3-LRCLK2_3-LRCLK2") (pintype "bidirectional"))
    )
    (net (code "54") (name "T_GPIO4") (class "Default")
      (node (ref "J3") (pin "3") (pinfunction "3_3") (pintype "passive"))
      (node (ref "U$1") (pin "4-BCLK2") (pinfunction "4-BCLK2_4-BCLK2") (pintype "bidirectional"))
    )
    (net (code "55") (name "T_GPIO5") (class "Default")
      (node (ref "J3") (pin "2") (pinfunction "2_2") (pintype "passive"))
      (node (ref "U$1") (pin "5-IN2") (pinfunction "5-IN2_5-IN2") (pintype "bidirectional"))
    )
    (net (code "56") (name "T_GPIO6") (class "Default")
      (node (ref "J3") (pin "1") (pinfunction "1_1") (pintype "passive"))
      (node (ref "U$1") (pin "6-OUT1D") (pinfunction "6-OUT1D_6-OUT1D") (pintype "bidirectional"))
    )
    (net (code "57") (name "T_PROGRAM") (class "Default")
      (node (ref "J11") (pin "2") (pinfunction "2_2") (pintype "passive"))
      (node (ref "U$1") (pin "PROGRAM") (pinfunction "PROGRAM_PROGRAM") (pintype "bidirectional"))
    )
    (net (code "58") (name "T_VBAT") (class "Default")
      (node (ref "J11") (pin "1") (pinfunction "1_1") (pintype "passive"))
      (node (ref "U$1") (pin "VBAT") (pinfunction "VBAT_VBAT") (pintype "bidirectional"))
    )
    (net (code "59") (name "T_VUSB") (class "Default")
      (node (ref "J12") (pin "1") (pinfunction "1_1") (pintype "passive"))
      (node (ref "U$1") (pin "VUSB") (pinfunction "VUSB_VUSB") (pintype "bidirectional"))
    )
    (net (code "60") (name "UART2_RXD") (class "Default")
      (node (ref "J2") (pin "1") (pinfunction "1_1") (pintype "passive"))
      (node (ref "U$1") (pin "34-RX8") (pinfunction "34-RX8_34-RX8") (pintype "bidirectional"))
    )
    (net (code "61") (name "UART2_TXD") (class "Default")
      (node (ref "J2") (pin "3") (pinfunction "3_3") (pintype "passive"))
      (node (ref "U$1") (pin "35-TX8") (pinfunction "35/TX8_35-TX8") (pintype "bidirectional"))
    )
    (net (code "62") (name "UART4_RXD") (class "Default")
      (node (ref "H1") (pin "1.1") (pinfunction "1.1_1.1") (pintype "bidirectional"))
      (node (ref "U$1") (pin "0-RX1/CS1/CRX2") (pinfunction "0-RX1/CS1/CRX2_0-RX1/CS1/CRX2") (pintype "bidirectional"))
    )
    (net (code "63") (name "UART4_TXD") (class "Default")
      (node (ref "H1") (pin "1.2") (pinfunction "1.2_1.2") (pintype "bidirectional"))
      (node (ref "U$1") (pin "1-TX1/MISO1/CTX2") (pinfunction "1-TX1/MISO1/CTX2_1-TX1/MISO1/CTX2") (pintype "bidirectional"))
    )
    (net (code "64") (name "UART5_RXD") (class "Default")
      (node (ref "J14") (pin "3") (pinfunction "3_3") (pintype "passive"))
      (node (ref "U$1") (pin "29-TX7") (pinfunction "29-TX7_29-TX7") (pintype "bidirectional"))
      (node (ref "U6") (pin "42") (pinfunction "GPS_RXDO_42") (pintype "input"))
    )
    (net (code "65") (name "UART5_TXD") (class "Default")
      (node (ref "J14") (pin "4") (pinfunction "4_4") (pintype "passive"))
      (node (ref "U$1") (pin "28-RX7") (pinfunction "28-RX7_28-RX7") (pintype "bidirectional"))
      (node (ref "U6") (pin "44") (pinfunction "GPS_TXD0_44") (pintype "output"))
    )
    (net (code "66") (name "USB_DEV_D+") (class "Default")
      (node (ref "J12") (pin "4") (pinfunction "4_4") (pintype "passive"))
      (node (ref "U$1") (pin "D+") (pinfunction "D+_D+") (pintype "bidirectional"))
    )
    (net (code "67") (name "USB_DEV_D-") (class "Default")
      (node (ref "J12") (pin "3") (pinfunction "3_3") (pintype "passive"))
      (node (ref "U$1") (pin "D-") (pinfunction "D-_D-") (pintype "bidirectional"))
    )
    (net (code "68") (name "USB_HOST_D+") (class "Default")
      (node (ref "J13") (pin "1") (pinfunction "1_1") (pintype "passive"))
      (node (ref "U$1") (pin "DP") (pinfunction "DP_DP") (pintype "bidirectional"))
    )
    (net (code "69") (name "USB_HOST_D-") (class "Default")
      (node (ref "J13") (pin "2") (pinfunction "2_2") (pintype "passive"))
      (node (ref "U$1") (pin "DM") (pinfunction "DM_DM") (pintype "bidirectional"))
    )
    (net (code "70") (name "unconnected-(H1-Pad1.9)") (class "Default")
      (node (ref "H1") (pin "1.9") (pinfunction "1.9_1.9") (pintype "bidirectional"))
    )
    (net (code "71") (name "unconnected-(H1-Pad1.10)") (class "Default")
      (node (ref "H1") (pin "1.10") (pinfunction "1.10_1.10") (pintype "bidirectional"))
    )
    (net (code "72") (name "unconnected-(H1-Pad1.11)") (class "Default")
      (node (ref "H1") (pin "1.11") (pinfunction "1.11_1.11") (pintype "bidirectional"))
    )
    (net (code "73") (name "unconnected-(H1-Pad1.12)") (class "Default")
      (node (ref "H1") (pin "1.12") (pinfunction "1.12_1.12") (pintype "bidirectional"))
    )
    (net (code "74") (name "unconnected-(H1-Pad1.13)") (class "Default")
      (node (ref "H1") (pin "1.13") (pinfunction "1.13_1.13") (pintype "bidirectional"))
    )
    (net (code "75") (name "unconnected-(H1-Pad1.14)") (class "Default")
      (node (ref "H1") (pin "1.14") (pinfunction "1.14_1.14") (pintype "bidirectional"))
    )
    (net (code "76") (name "unconnected-(H1-Pad1.15)") (class "Default")
      (node (ref "H1") (pin "1.15") (pinfunction "1.15_1.15") (pintype "bidirectional"))
    )
    (net (code "77") (name "unconnected-(H1-Pad1.16)") (class "Default")
      (node (ref "H1") (pin "1.16") (pinfunction "1.16_1.16") (pintype "bidirectional"))
    )
    (net (code "78") (name "unconnected-(H1-Pad1.17)") (class "Default")
      (node (ref "H1") (pin "1.17") (pinfunction "1.17_1.17") (pintype "bidirectional"))
    )
    (net (code "79") (name "unconnected-(H1-Pad1.18)") (class "Default")
      (node (ref "H1") (pin "1.18") (pinfunction "1.18_1.18") (pintype "bidirectional"))
    )
    (net (code "80") (name "unconnected-(H1-Pad1.19)") (class "Default")
      (node (ref "H1") (pin "1.19") (pinfunction "1.19_1.19") (pintype "bidirectional"))
    )
    (net (code "81") (name "unconnected-(H1-Pad1.20)") (class "Default")
      (node (ref "H1") (pin "1.20") (pinfunction "1.20_1.20") (pintype "bidirectional"))
    )
    (net (code "82") (name "unconnected-(H1-Pad1.21)") (class "Default")
      (node (ref "H1") (pin "1.21") (pinfunction "1.21_1.21") (pintype "bidirectional"))
    )
    (net (code "83") (name "unconnected-(H1-Pad1.22)") (class "Default")
      (node (ref "H1") (pin "1.22") (pinfunction "1.22_1.22") (pintype "bidirectional"))
    )
    (net (code "84") (name "unconnected-(H1-Pad1.23)") (class "Default")
      (node (ref "H1") (pin "1.23") (pinfunction "1.23_1.23") (pintype "bidirectional"))
    )
    (net (code "85") (name "unconnected-(H1-Pad1.24)") (class "Default")
      (node (ref "H1") (pin "1.24") (pinfunction "1.24_1.24") (pintype "bidirectional"))
    )
    (net (code "86") (name "unconnected-(H1-Pad1.25)") (class "Default")
      (node (ref "H1") (pin "1.25") (pinfunction "1.25_1.25") (pintype "bidirectional"))
    )
    (net (code "87") (name "unconnected-(H1-Pad1.26)") (class "Default")
      (node (ref "H1") (pin "1.26") (pinfunction "1.26_1.26") (pintype "bidirectional"))
    )
    (net (code "88") (name "unconnected-(H1-Pad1.27)") (class "Default")
      (node (ref "H1") (pin "1.27") (pinfunction "1.27_1.27") (pintype "bidirectional"))
    )
    (net (code "89") (name "unconnected-(H1-Pad1.28)") (class "Default")
      (node (ref "H1") (pin "1.28") (pinfunction "1.28_1.28") (pintype "bidirectional"))
    )
    (net (code "90") (name "unconnected-(H1-Pad1.29)") (class "Default")
      (node (ref "H1") (pin "1.29") (pinfunction "1.29_1.29") (pintype "bidirectional"))
    )
    (net (code "91") (name "unconnected-(H1-Pad1.30)") (class "Default")
      (node (ref "H1") (pin "1.30") (pinfunction "1.30_1.30") (pintype "bidirectional"))
    )
    (net (code "92") (name "unconnected-(H1-Pad1.31)") (class "Default")
      (node (ref "H1") (pin "1.31") (pinfunction "1.31_1.31") (pintype "bidirectional"))
    )
    (net (code "93") (name "unconnected-(H1-Pad1.32)") (class "Default")
      (node (ref "H1") (pin "1.32") (pinfunction "1.32_1.32") (pintype "bidirectional"))
    )
    (net (code "94") (name "unconnected-(H1-Pad1.33)") (class "Default")
      (node (ref "H1") (pin "1.33") (pinfunction "1.33_1.33") (pintype "bidirectional"))
    )
    (net (code "95") (name "unconnected-(H1-Pad1.34)") (class "Default")
      (node (ref "H1") (pin "1.34") (pinfunction "1.34_1.34") (pintype "bidirectional"))
    )
    (net (code "96") (name "unconnected-(H1-Pad1.35)") (class "Default")
      (node (ref "H1") (pin "1.35") (pinfunction "1.35_1.35") (pintype "bidirectional"))
    )
    (net (code "97") (name "unconnected-(H1-Pad1.36)") (class "Default")
      (node (ref "H1") (pin "1.36") (pinfunction "1.36_1.36") (pintype "bidirectional"))
    )
    (net (code "98") (name "unconnected-(H1-Pad1.37)") (class "Default")
      (node (ref "H1") (pin "1.37") (pinfunction "1.37_1.37") (pintype "bidirectional"))
    )
    (net (code "99") (name "unconnected-(H1-Pad1.38)") (class "Default")
      (node (ref "H1") (pin "1.38") (pinfunction "1.38_1.38") (pintype "bidirectional"))
    )
    (net (code "100") (name "unconnected-(H1-Pad1.39)") (class "Default")
      (node (ref "H1") (pin "1.39") (pinfunction "1.39_1.39") (pintype "bidirectional"))
    )
    (net (code "101") (name "unconnected-(H1-Pad1.40)") (class "Default")
      (node (ref "H1") (pin "1.40") (pinfunction "1.40_1.40") (pintype "bidirectional"))
    )
    (net (code "102") (name "unconnected-(H1-Pad1.42)") (class "Default")
      (node (ref "H1") (pin "1.42") (pinfunction "1.42_1.42") (pintype "bidirectional"))
    )
    (net (code "103") (name "unconnected-(H1-Pad1.44)") (class "Default")
      (node (ref "H1") (pin "1.44") (pinfunction "1.44_1.44") (pintype "bidirectional"))
    )
    (net (code "104") (name "unconnected-(H1-Pad1.45)") (class "Default")
      (node (ref "H1") (pin "1.45") (pinfunction "1.45_1.45") (pintype "bidirectional"))
    )
    (net (code "105") (name "unconnected-(H1-Pad1.46)") (class "Default")
      (node (ref "H1") (pin "1.46") (pinfunction "1.46_1.46") (pintype "bidirectional"))
    )
    (net (code "106") (name "unconnected-(H1-Pad1.47)") (class "Default")
      (node (ref "H1") (pin "1.47") (pinfunction "1.47_1.47") (pintype "bidirectional"))
    )
    (net (code "107") (name "unconnected-(H1-Pad1.48)") (class "Default")
      (node (ref "H1") (pin "1.48") (pinfunction "1.48_1.48") (pintype "bidirectional"))
    )
    (net (code "108") (name "unconnected-(H1-Pad1.49)") (class "Default")
      (node (ref "H1") (pin "1.49") (pinfunction "1.49_1.49") (pintype "bidirectional"))
    )
    (net (code "109") (name "unconnected-(H1-Pad1.50)") (class "Default")
      (node (ref "H1") (pin "1.50") (pinfunction "1.50_1.50") (pintype "bidirectional"))
    )
    (net (code "110") (name "unconnected-(H1-Pad1.51)") (class "Default")
      (node (ref "H1") (pin "1.51") (pinfunction "1.51_1.51") (pintype "bidirectional"))
    )
    (net (code "111") (name "unconnected-(H1-Pad1.52)") (class "Default")
      (node (ref "H1") (pin "1.52") (pinfunction "1.52_1.52") (pintype "bidirectional"))
    )
    (net (code "112") (name "unconnected-(H1-Pad2.1)") (class "Default")
      (node (ref "H1") (pin "2.1") (pinfunction "2.1_2.1") (pintype "bidirectional"))
    )
    (net (code "113") (name "unconnected-(H1-Pad2.2)") (class "Default")
      (node (ref "H1") (pin "2.2") (pinfunction "2.2_2.2") (pintype "bidirectional"))
    )
    (net (code "114") (name "unconnected-(H1-Pad2.3)") (class "Default")
      (node (ref "H1") (pin "2.3") (pinfunction "2.3_2.3") (pintype "bidirectional"))
    )
    (net (code "115") (name "unconnected-(H1-Pad2.4)") (class "Default")
      (node (ref "H1") (pin "2.4") (pinfunction "2.4_2.4") (pintype "bidirectional"))
    )
    (net (code "116") (name "unconnected-(H1-Pad2.5)") (class "Default")
      (node (ref "H1") (pin "2.5") (pinfunction "2.5_2.5") (pintype "bidirectional"))
    )
    (net (code "117") (name "unconnected-(H1-Pad2.6)") (class "Default")
      (node (ref "H1") (pin "2.6") (pinfunction "2.6_2.6") (pintype "bidirectional"))
    )
    (net (code "118") (name "unconnected-(H1-Pad2.8)") (class "Default")
      (node (ref "H1") (pin "2.8") (pinfunction "2.8_2.8") (pintype "bidirectional"))
    )
    (net (code "119") (name "unconnected-(H1-Pad2.9)") (class "Default")
      (node (ref "H1") (pin "2.9") (pinfunction "2.9_2.9") (pintype "bidirectional"))
    )
    (net (code "120") (name "unconnected-(H1-Pad2.10)") (class "Default")
      (node (ref "H1") (pin "2.10") (pinfunction "2.10_2.10") (pintype "bidirectional"))
    )
    (net (code "121") (name "unconnected-(H1-Pad2.11)") (class "Default")
      (node (ref "H1") (pin "2.11") (pinfunction "2.11_2.11") (pintype "bidirectional"))
    )
    (net (code "122") (name "unconnected-(H1-Pad2.12)") (class "Default")
      (node (ref "H1") (pin "2.12") (pinfunction "2.12_2.12") (pintype "bidirectional"))
    )
    (net (code "123") (name "unconnected-(H1-Pad2.13)") (class "Default")
      (node (ref "H1") (pin "2.13") (pinfunction "2.13_2.13") (pintype "bidirectional"))
    )
    (net (code "124") (name "unconnected-(H1-Pad2.15)") (class "Default")
      (node (ref "H1") (pin "2.15") (pinfunction "2.15_2.15") (pintype "bidirectional"))
    )
    (net (code "125") (name "unconnected-(H1-Pad2.16)") (class "Default")
      (node (ref "H1") (pin "2.16") (pinfunction "2.16_2.16") (pintype "bidirectional"))
    )
    (net (code "126") (name "unconnected-(H1-Pad2.18)") (class "Default")
      (node (ref "H1") (pin "2.18") (pinfunction "2.18_2.18") (pintype "bidirectional"))
    )
    (net (code "127") (name "unconnected-(H1-Pad2.19)") (class "Default")
      (node (ref "H1") (pin "2.19") (pinfunction "2.19_2.19") (pintype "bidirectional"))
    )
    (net (code "128") (name "unconnected-(H1-Pad2.20)") (class "Default")
      (node (ref "H1") (pin "2.20") (pinfunction "2.20_2.20") (pintype "bidirectional"))
    )
    (net (code "129") (name "unconnected-(H1-Pad2.23)") (class "Default")
      (node (ref "H1") (pin "2.23") (pinfunction "2.23_2.23") (pintype "bidirectional"))
    )
    (net (code "130") (name "unconnected-(H1-Pad2.24)") (class "Default")
      (node (ref "H1") (pin "2.24") (pinfunction "2.24_2.24") (pintype "bidirectional"))
    )
    (net (code "131") (name "unconnected-(H1-Pad2.31)") (class "Default")
      (node (ref "H1") (pin "2.31") (pinfunction "2.31_2.31") (pintype "bidirectional"))
    )
    (net (code "132") (name "unconnected-(H1-Pad2.33)") (class "Default")
      (node (ref "H1") (pin "2.33") (pinfunction "2.33_2.33") (pintype "bidirectional"))
    )
    (net (code "133") (name "unconnected-(H1-Pad2.34)") (class "Default")
      (node (ref "H1") (pin "2.34") (pinfunction "2.34_2.34") (pintype "bidirectional"))
    )
    (net (code "134") (name "unconnected-(H1-Pad2.35)") (class "Default")
      (node (ref "H1") (pin "2.35") (pinfunction "2.35_2.35") (pintype "bidirectional"))
    )
    (net (code "135") (name "unconnected-(H1-Pad2.36)") (class "Default")
      (node (ref "H1") (pin "2.36") (pinfunction "2.36_2.36") (pintype "bidirectional"))
    )
    (net (code "136") (name "unconnected-(H1-Pad2.37)") (class "Default")
      (node (ref "H1") (pin "2.37") (pinfunction "2.37_2.37") (pintype "bidirectional"))
    )
    (net (code "137") (name "unconnected-(H1-Pad2.38)") (class "Default")
      (node (ref "H1") (pin "2.38") (pinfunction "2.38_2.38") (pintype "bidirectional"))
    )
    (net (code "138") (name "unconnected-(H1-Pad2.39)") (class "Default")
      (node (ref "H1") (pin "2.39") (pinfunction "2.39_2.39") (pintype "bidirectional"))
    )
    (net (code "139") (name "unconnected-(H1-Pad2.40)") (class "Default")
      (node (ref "H1") (pin "2.40") (pinfunction "2.40_2.40") (pintype "bidirectional"))
    )
    (net (code "140") (name "unconnected-(H1-Pad2.41)") (class "Default")
      (node (ref "H1") (pin "2.41") (pinfunction "2.41_2.41") (pintype "bidirectional"))
    )
    (net (code "141") (name "unconnected-(H1-Pad2.42)") (class "Default")
      (node (ref "H1") (pin "2.42") (pinfunction "2.42_2.42") (pintype "bidirectional"))
    )
    (net (code "142") (name "unconnected-(H1-Pad2.43)") (class "Default")
      (node (ref "H1") (pin "2.43") (pinfunction "2.43_2.43") (pintype "bidirectional"))
    )
    (net (code "143") (name "unconnected-(H1-Pad2.44)") (class "Default")
      (node (ref "H1") (pin "2.44") (pinfunction "2.44_2.44") (pintype "bidirectional"))
    )
    (net (code "144") (name "unconnected-(H1-Pad2.45)") (class "Default")
      (node (ref "H1") (pin "2.45") (pinfunction "2.45_2.45") (pintype "bidirectional"))
    )
    (net (code "145") (name "unconnected-(H1-Pad2.46)") (class "Default")
      (node (ref "H1") (pin "2.46") (pinfunction "2.46_2.46") (pintype "bidirectional"))
    )
    (net (code "146") (name "unconnected-(H1-Pad2.49)") (class "Default")
      (node (ref "H1") (pin "2.49") (pinfunction "2.49_2.49") (pintype "bidirectional"))
    )
    (net (code "147") (name "unconnected-(H1-Pad2.50)") (class "Default")
      (node (ref "H1") (pin "2.50") (pinfunction "2.50_2.50") (pintype "bidirectional"))
    )
    (net (code "148") (name "unconnected-(H1-Pad2.51)") (class "Default")
      (node (ref "H1") (pin "2.51") (pinfunction "2.51_2.51") (pintype "bidirectional"))
    )
    (net (code "149") (name "unconnected-(H1-Pad2.52)") (class "Default")
      (node (ref "H1") (pin "2.52") (pinfunction "2.52_2.52") (pintype "bidirectional"))
    )
    (net (code "150") (name "unconnected-(H1-PadP$1)") (class "Default")
      (node (ref "H1") (pin "P$1") (pinfunction "P$1_P$1") (pintype "bidirectional"))
    )
    (net (code "151") (name "unconnected-(H1-PadP$2)") (class "Default")
      (node (ref "H1") (pin "P$2") (pinfunction "P$2_P$2") (pintype "bidirectional"))
    )
    (net (code "152") (name "unconnected-(H1-PadP$3)") (class "Default")
      (node (ref "H1") (pin "P$3") (pinfunction "P$3_P$3") (pintype "bidirectional"))
    )
    (net (code "153") (name "unconnected-(U$1-Pad9-OUT1C)") (class "Default")
      (node (ref "U$1") (pin "9-OUT1C") (pinfunction "9-OUT1C_9-OUT1C") (pintype "bidirectional"))
    )
    (net (code "154") (name "unconnected-(U$1-Pad30-CRX3)") (class "Default")
      (node (ref "U$1") (pin "30-CRX3") (pinfunction "30-CRX3_30-CRX3") (pintype "bidirectional"))
    )
    (net (code "155") (name "unconnected-(U$1-Pad31-CTX3)") (class "Default")
      (node (ref "U$1") (pin "31-CTX3") (pinfunction "31-CTX3_31-CTX3") (pintype "bidirectional"))
    )
    (net (code "156") (name "unconnected-(U$1-Pad32-OUT1B)") (class "Default")
      (node (ref "U$1") (pin "32-OUT1B") (pinfunction "32-OUT1B_32-OUT1B") (pintype "bidirectional"))
    )
    (net (code "157") (name "unconnected-(U$1-Pad37-PWM)") (class "Default")
      (node (ref "U$1") (pin "37-PWM") (pinfunction "37-PWM_37-PWM") (pintype "bidirectional"))
    )
    (net (code "158") (name "unconnected-(U$1-Pad40-A16{slash}CS1)") (class "Default")
      (node (ref "U$1") (pin "40-A16/CS1") (pinfunction "40-A16/CS1_40-A16/CS1") (pintype "bidirectional"))
    )
    (net (code "159") (name "unconnected-(U$1-PadON{slash}OFF)") (class "Default")
      (node (ref "U$1") (pin "ON/OFF") (pinfunction "ON/OFF_ON/OFF") (pintype "bidirectional"))
    )
    (net (code "160") (name "unconnected-(U1-NC-Pad7)") (class "Default")
      (node (ref "U1") (pin "7") (pinfunction "NC_7") (pintype "no_connect"))
    )
    (net (code "161") (name "unconnected-(U1-NC_2-Pad2)") (class "Default")
      (node (ref "U1") (pin "2") (pinfunction "NC_2_2") (pintype "no_connect"))
    )
    (net (code "162") (name "unconnected-(U1-NC_3-Pad3)") (class "Default")
      (node (ref "U1") (pin "3") (pinfunction "NC_3_3") (pintype "no_connect"))
    )
    (net (code "163") (name "unconnected-(U1-NC_4-Pad6)") (class "Default")
      (node (ref "U1") (pin "6") (pinfunction "NC_4_6") (pintype "no_connect"))
    )
    (net (code "164") (name "unconnected-(U3-DIO1-Pad11)") (class "Default")
      (node (ref "U3") (pin "11") (pinfunction "DIO1_11") (pintype "bidirectional"))
    )
    (net (code "165") (name "unconnected-(U3-DIO2-Pad12)") (class "Default")
      (node (ref "U3") (pin "12") (pinfunction "DIO2_12") (pintype "bidirectional"))
    )
    (net (code "166") (name "unconnected-(U3-DIO3-Pad13)") (class "Default")
      (node (ref "U3") (pin "13") (pinfunction "DIO3_13") (pintype "bidirectional"))
    )
    (net (code "167") (name "unconnected-(U3-DIO4-Pad14)") (class "Default")
      (node (ref "U3") (pin "14") (pinfunction "DIO4_14") (pintype "bidirectional"))
    )
    (net (code "168") (name "unconnected-(U3-DIO5-Pad15)") (class "Default")
      (node (ref "U3") (pin "15") (pinfunction "DIO5_15") (pintype "bidirectional"))
    )
    (net (code "169") (name "unconnected-(U3-NC-Pad1)") (class "Default")
      (node (ref "U3") (pin "1") (pinfunction "NC_1") (pintype "bidirectional"))
    )
    (net (code "170") (name "unconnected-(U5-Pad1)") (class "Default")
      (node (ref "U5") (pin "1") (pinfunction "1_1") (pintype "passive"))
    )
    (net (code "171") (name "unconnected-(U6-P$3-Pad3)") (class "Default")
      (node (ref "U6") (pin "3") (pinfunction "P$3_3") (pintype "bidirectional"))
    )
    (net (code "172") (name "unconnected-(U6-P$4-Pad4)") (class "Default")
      (node (ref "U6") (pin "4") (pinfunction "P$4_4") (pintype "bidirectional"))
    )
    (net (code "173") (name "unconnected-(U6-P$5-Pad5)") (class "Default")
      (node (ref "U6") (pin "5") (pinfunction "P$5_5") (pintype "bidirectional"))
    )
    (net (code "174") (name "unconnected-(U6-P$6-Pad6)") (class "Default")
      (node (ref "U6") (pin "6") (pinfunction "P$6_6") (pintype "bidirectional"))
    )
    (net (code "175") (name "unconnected-(U6-P$8-Pad8)") (class "Default")
      (node (ref "U6") (pin "8") (pinfunction "P$8_8") (pintype "bidirectional"))
    )
    (net (code "176") (name "unconnected-(U6-P$12-Pad12)") (class "Default")
      (node (ref "U6") (pin "12") (pinfunction "P$12_12") (pintype "bidirectional"))
    )
    (net (code "177") (name "unconnected-(U6-P$13-Pad13)") (class "Default")
      (node (ref "U6") (pin "13") (pinfunction "P$13_13") (pintype "bidirectional"))
    )
    (net (code "178") (name "unconnected-(U6-P$14-Pad14)") (class "Default")
      (node (ref "U6") (pin "14") (pinfunction "P$14_14") (pintype "bidirectional"))
    )
    (net (code "179") (name "unconnected-(U6-P$16-Pad16)") (class "Default")
      (node (ref "U6") (pin "16") (pinfunction "P$16_16") (pintype "bidirectional"))
    )
    (net (code "180") (name "unconnected-(U6-P$17-Pad17)") (class "Default")
      (node (ref "U6") (pin "17") (pinfunction "P$17_17") (pintype "bidirectional"))
    )
    (net (code "181") (name "unconnected-(U6-P$20-Pad20)") (class "Default")
      (node (ref "U6") (pin "20") (pinfunction "P$20_20") (pintype "bidirectional"))
    )
    (net (code "182") (name "unconnected-(U6-P$23-Pad23)") (class "Default")
      (node (ref "U6") (pin "23") (pinfunction "P$23_23") (pintype "bidirectional"))
    )
    (net (code "183") (name "unconnected-(U6-P$26-Pad26)") (class "Default")
      (node (ref "U6") (pin "26") (pinfunction "P$26_26") (pintype "bidirectional"))
    )
    (net (code "184") (name "unconnected-(U6-P$30-Pad30)") (class "Default")
      (node (ref "U6") (pin "30") (pinfunction "P$30_30") (pintype "bidirectional"))
    )
    (net (code "185") (name "unconnected-(U6-P$34-Pad34)") (class "Default")
      (node (ref "U6") (pin "34") (pinfunction "P$34_34") (pintype "bidirectional"))
    )
    (net (code "186") (name "unconnected-(U6-P$35-Pad35)") (class "Default")
      (node (ref "U6") (pin "35") (pinfunction "P$35_35") (pintype "bidirectional"))
    )
    (net (code "187") (name "unconnected-(U6-P$36-Pad36)") (class "Default")
      (node (ref "U6") (pin "36") (pinfunction "P$36_36") (pintype "bidirectional"))
    )
    (net (code "188") (name "unconnected-(U6-P$37-Pad37)") (class "Default")
      (node (ref "U6") (pin "37") (pinfunction "P$37_37") (pintype "bidirectional"))
    )
    (net (code "189") (name "unconnected-(U6-P$38-Pad38)") (class "Default")
      (node (ref "U6") (pin "38") (pinfunction "P$38_38") (pintype "bidirectional"))
    )
    (net (code "190") (name "unconnected-(U6-P$39-Pad39)") (class "Default")
      (node (ref "U6") (pin "39") (pinfunction "P$39_39") (pintype "bidirectional"))
    )
    (net (code "191") (name "unconnected-(U6-P$40-Pad40)") (class "Default")
      (node (ref "U6") (pin "40") (pinfunction "P$40_40") (pintype "bidirectional"))
    )
    (net (code "192") (name "unconnected-(U6-P$41-Pad41)") (class "Default")
      (node (ref "U6") (pin "41") (pinfunction "P$41_41") (pintype "bidirectional"))
    )
    (net (code "193") (name "unconnected-(U6-P$43-Pad43)") (class "Default")
      (node (ref "U6") (pin "43") (pinfunction "P$43_43") (pintype "bidirectional"))
    )
    (net (code "194") (name "unconnected-(U6-P$45-Pad45)") (class "Default")
      (node (ref "U6") (pin "45") (pinfunction "P$45_45") (pintype "bidirectional"))
    )
    (net (code "195") (name "unconnected-(U6-P$46-Pad46)") (class "Default")
      (node (ref "U6") (pin "46") (pinfunction "P$46_46") (pintype "bidirectional"))
    )
    (net (code "196") (name "unconnected-(U6-P$47-Pad47)") (class "Default")
      (node (ref "U6") (pin "47") (pinfunction "P$47_47") (pintype "bidirectional"))
    )
    (net (code "197") (name "unconnected-(U6-P$48-Pad48)") (class "Default")
      (node (ref "U6") (pin "48") (pinfunction "P$48_48") (pintype "bidirectional"))
    )
    (net (code "198") (name "unconnected-(U6-P$49-Pad49)") (class "Default")
      (node (ref "U6") (pin "49") (pinfunction "P$49_49") (pintype "bidirectional"))
    )
    (net (code "199") (name "unconnected-(U6-P$50-Pad50)") (class "Default")
      (node (ref "U6") (pin "50") (pinfunction "P$50_50") (pintype "bidirectional"))
    )
    (net (code "200") (name "unconnected-(U6-P$51-Pad51)") (class "Default")
      (node (ref "U6") (pin "51") (pinfunction "P$51_51") (pintype "bidirectional"))
    )
    (net (code "201") (name "unconnected-(U6-P$52-Pad52)") (class "Default")
      (node (ref "U6") (pin "52") (pinfunction "P$52_52") (pintype "bidirectional"))
    )
    (net (code "202") (name "unconnected-(U6-P$53-Pad53)") (class "Default")
      (node (ref "U6") (pin "53") (pinfunction "P$53_53") (pintype "bidirectional"))
    )
    (net (code "203") (name "unconnected-(U6-P$54-Pad54)") (class "Default")
      (node (ref "U6") (pin "54") (pinfunction "P$54_54") (pintype "bidirectional"))
    )
    (net (code "204") (name "unconnected-(U6-P$55-Pad55)") (class "Default")
      (node (ref "U6") (pin "55") (pinfunction "P$55_55") (pintype "bidirectional"))
    )
    (net (code "205") (name "unconnected-(U6-P$56-Pad56)") (class "Default")
      (node (ref "U6") (pin "56") (pinfunction "P$56_56") (pintype "bidirectional"))
    )
    (net (code "206") (name "unconnected-(U6-P$57-Pad57)") (class "Default")
      (node (ref "U6") (pin "57") (pinfunction "P$57_57") (pintype "bidirectional"))
    )
    (net (code "207") (name "unconnected-(U6-P$59-Pad59)") (class "Default")
      (node (ref "U6") (pin "59") (pinfunction "P$59_59") (pintype "bidirectional"))
    )
    (net (code "208") (name "unconnected-(U6-P$60-Pad60)") (class "Default")
      (node (ref "U6") (pin "60") (pinfunction "P$60_60") (pintype "bidirectional"))
    )
    (net (code "209") (name "unconnected-(U6-P$61-Pad61)") (class "Default")
      (node (ref "U6") (pin "61") (pinfunction "P$61_61") (pintype "bidirectional"))
    )
    (net (code "210") (name "unconnected-(U6-P$62-Pad62)") (class "Default")
      (node (ref "U6") (pin "62") (pinfunction "P$62_62") (pintype "bidirectional"))
    )
    (net (code "211") (name "unconnected-(U6-P$63-Pad63)") (class "Default")
      (node (ref "U6") (pin "63") (pinfunction "P$63_63") (pintype "bidirectional"))
    )
    (net (code "212") (name "unconnected-(U6-P$65-Pad65)") (class "Default")
      (node (ref "U6") (pin "65") (pinfunction "P$65_65") (pintype "bidirectional"))
    )
    (net (code "213") (name "unconnected-(U6-P$66-Pad66)") (class "Default")
      (node (ref "U6") (pin "66") (pinfunction "P$66_66") (pintype "bidirectional"))
    )
    (net (code "214") (name "unconnected-(U6-P$67-Pad67)") (class "Default")
      (node (ref "U6") (pin "67") (pinfunction "P$67_67") (pintype "bidirectional"))
    )
    (net (code "215") (name "unconnected-(U6-P$68-Pad68)") (class "Default")
      (node (ref "U6") (pin "68") (pinfunction "P$68_68") (pintype "bidirectional"))
    )
    (net (code "216") (name "unconnected-(U6-P$69-Pad69)") (class "Default")
      (node (ref "U6") (pin "69") (pinfunction "P$69_69") (pintype "bidirectional"))
    )
    (net (code "217") (name "unconnected-(X1-P$1-Pad1)") (class "Default")
      (node (ref "X1") (pin "1") (pinfunction "P$1_1") (pintype "bidirectional"))
    )
    (net (code "218") (name "unconnected-(X1-P$4-Pad4)") (class "Default")
      (node (ref "X1") (pin "4") (pinfunction "P$4_4") (pintype "bidirectional"))
    )
    (net (code "219") (name "unconnected-(X1-P$6-Pad6)") (class "Default")
      (node (ref "X1") (pin "6") (pinfunction "P$6_6") (pintype "bidirectional"))
    )
    (net (code "220") (name "unconnected-(X1-P$7-Pad7)") (class "Default")
      (node (ref "X1") (pin "7") (pinfunction "P$7_7") (pintype "bidirectional"))
    )
    (net (code "221") (name "unconnected-(X1-P$8-Pad8)") (class "Default")
      (node (ref "X1") (pin "8") (pinfunction "P$8_8") (pintype "bidirectional"))
    )
    (net (code "222") (name "unconnected-(X1-P$9-Pad9)") (class "Default")
      (node (ref "X1") (pin "9") (pinfunction "P$9_9") (pintype "bidirectional"))
    )
    (net (code "223") (name "unconnected-(X1-P$10-Pad10)") (class "Default")
      (node (ref "X1") (pin "10") (pinfunction "P$10_10") (pintype "bidirectional"))
    )
    (net (code "224") (name "unconnected-(X1-P$12-Pad12)") (class "Default")
      (node (ref "X1") (pin "12") (pinfunction "P$12_12") (pintype "bidirectional"))
    )
    (net (code "225") (name "unconnected-(X1-P$14-Pad14)") (class "Default")
      (node (ref "X1") (pin "14") (pinfunction "P$14_14") (pintype "bidirectional"))
    )
    (net (code "226") (name "unconnected-(X1-P$17-Pad17)") (class "Default")
      (node (ref "X1") (pin "17") (pinfunction "P$17_17") (pintype "bidirectional"))
    )
    (net (code "227") (name "unconnected-(X1-P$20-Pad20)") (class "Default")
      (node (ref "X1") (pin "20") (pinfunction "P$20_20") (pintype "bidirectional"))
    )
    (net (code "228") (name "unconnected-(X1-P$25-Pad25)") (class "Default")
      (node (ref "X1") (pin "25") (pinfunction "P$25_25") (pintype "bidirectional"))
    )
    (net (code "229") (name "unconnected-(X1-P$27-Pad27)") (class "Default")
      (node (ref "X1") (pin "27") (pinfunction "P$27_27") (pintype "bidirectional"))
    )
    (net (code "230") (name "unconnected-(X1-P$28-Pad28)") (class "Default")
      (node (ref "X1") (pin "28") (pinfunction "P$28_28") (pintype "bidirectional"))
    )
    (net (code "231") (name "unconnected-(X1-P$29-Pad29)") (class "Default")
      (node (ref "X1") (pin "29") (pinfunction "P$29_29") (pintype "bidirectional"))
    )
    (net (code "232") (name "unconnected-(X1-P$30-Pad30)") (class "Default")
      (node (ref "X1") (pin "30") (pinfunction "P$30_30") (pintype "bidirectional"))
    )
    (net (code "233") (name "unconnected-(X1-P$31-Pad31)") (class "Default")
      (node (ref "X1") (pin "31") (pinfunction "P$31_31") (pintype "bidirectional"))
    )
    (net (code "234") (name "unconnected-(X1-P$32-Pad32)") (class "Default")
      (node (ref "X1") (pin "32") (pinfunction "P$32_32") (pintype "bidirectional"))
    )
    (net (code "235") (name "unconnected-(X1-P$33-Pad33)") (class "Default")
      (node (ref "X1") (pin "33") (pinfunction "P$33_33") (pintype "bidirectional"))
    )
    (net (code "236") (name "unconnected-(X1-P$34-Pad34)") (class "Default")
      (node (ref "X1") (pin "34") (pinfunction "P$34_34") (pintype "bidirectional"))
    )
    (net (code "237") (name "unconnected-(X1-P$35-Pad35)") (class "Default")
      (node (ref "X1") (pin "35") (pinfunction "P$35_35") (pintype "bidirectional"))
    )
    (net (code "238") (name "unconnected-(X1-P$36-Pad36)") (class "Default")
      (node (ref "X1") (pin "36") (pinfunction "P$36_36") (pintype "bidirectional"))
    )
    (net (code "239") (name "unconnected-(X1-P$37-Pad37)") (class "Default")
      (node (ref "X1") (pin "37") (pinfunction "P$37_37") (pintype "bidirectional"))
    )
    (net (code "240") (name "unconnected-(X1-P$38-Pad38)") (class "Default")
      (node (ref "X1") (pin "38") (pinfunction "P$38_38") (pintype "bidirectional"))
    )
    (net (code "241") (name "unconnected-(X1-P$40-Pad40)") (class "Default")
      (node (ref "X1") (pin "40") (pinfunction "P$40_40") (pintype "bidirectional"))
    )
    (net (code "242") (name "unconnected-(X2-Pad1)") (class "Default")
      (node (ref "X2") (pin "1") (pinfunction "1_1") (pintype "passive"))
    )
    (net (code "243") (name "unconnected-(X2AA-1-Pad33)") (class "Default")
      (node (ref "X2") (pin "33") (pinfunction "1_33") (pintype "passive"))
    )
    (net (code "244") (name "unconnected-(X2AB-1-Pad34)") (class "Default")
      (node (ref "X2") (pin "34") (pinfunction "1_34") (pintype "passive"))
    )
    (net (code "245") (name "unconnected-(X2AC-1-Pad35)") (class "Default")
      (node (ref "X2") (pin "35") (pinfunction "1_35") (pintype "passive"))
    )
    (net (code "246") (name "unconnected-(X2AD-1-Pad36)") (class "Default")
      (node (ref "X2") (pin "36") (pinfunction "1_36") (pintype "passive"))
    )
    (net (code "247") (name "unconnected-(X2AE-1-Pad37)") (class "Default")
      (node (ref "X2") (pin "37") (pinfunction "1_37") (pintype "passive"))
    )
    (net (code "248") (name "unconnected-(X2AF-1-Pad38)") (class "Default")
      (node (ref "X2") (pin "38") (pinfunction "1_38") (pintype "passive"))
    )
    (net (code "249") (name "unconnected-(X2AG-1-Pad39)") (class "Default")
      (node (ref "X2") (pin "39") (pinfunction "1_39") (pintype "passive"))
    )
    (net (code "250") (name "unconnected-(X2AH-1-Pad4)") (class "Default")
      (node (ref "X2") (pin "4") (pinfunction "1_4") (pintype "passive"))
    )
    (net (code "251") (name "unconnected-(X2AI-1-Pad40)") (class "Default")
      (node (ref "X2") (pin "40") (pinfunction "1_40") (pintype "passive"))
    )
    (net (code "252") (name "unconnected-(X2AJ-1-Pad5)") (class "Default")
      (node (ref "X2") (pin "5") (pinfunction "1_5") (pintype "passive"))
    )
    (net (code "253") (name "unconnected-(X2AK-1-Pad6)") (class "Default")
      (node (ref "X2") (pin "6") (pinfunction "1_6") (pintype "passive"))
    )
    (net (code "254") (name "unconnected-(X2AL-1-Pad7)") (class "Default")
      (node (ref "X2") (pin "7") (pinfunction "1_7") (pintype "passive"))
    )
    (net (code "255") (name "unconnected-(X2AM-1-Pad8)") (class "Default")
      (node (ref "X2") (pin "8") (pinfunction "1_8") (pintype "passive"))
    )
    (net (code "256") (name "unconnected-(X2AN-1-Pad9)") (class "Default")
      (node (ref "X2") (pin "9") (pinfunction "1_9") (pintype "passive"))
    )
    (net (code "257") (name "unconnected-(X2B-1-Pad10)") (class "Default")
      (node (ref "X2") (pin "10") (pinfunction "1_10") (pintype "passive"))
    )
    (net (code "258") (name "unconnected-(X2C-1-Pad11)") (class "Default")
      (node (ref "X2") (pin "11") (pinfunction "1_11") (pintype "passive"))
    )
    (net (code "259") (name "unconnected-(X2D-1-Pad12)") (class "Default")
      (node (ref "X2") (pin "12") (pinfunction "1_12") (pintype "passive"))
    )
    (net (code "260") (name "unconnected-(X2E-1-Pad13)") (class "Default")
      (node (ref "X2") (pin "13") (pinfunction "1_13") (pintype "passive"))
    )
    (net (code "261") (name "unconnected-(X2F-1-Pad14)") (class "Default")
      (node (ref "X2") (pin "14") (pinfunction "1_14") (pintype "passive"))
    )
    (net (code "262") (name "unconnected-(X2G-1-Pad15)") (class "Default")
      (node (ref "X2") (pin "15") (pinfunction "1_15") (pintype "passive"))
    )
    (net (code "263") (name "unconnected-(X2H-1-Pad16)") (class "Default")
      (node (ref "X2") (pin "16") (pinfunction "1_16") (pintype "passive"))
    )
    (net (code "264") (name "unconnected-(X2I-1-Pad17)") (class "Default")
      (node (ref "X2") (pin "17") (pinfunction "1_17") (pintype "passive"))
    )
    (net (code "265") (name "unconnected-(X2J-1-Pad18)") (class "Default")
      (node (ref "X2") (pin "18") (pinfunction "1_18") (pintype "passive"))
    )
    (net (code "266") (name "unconnected-(X2K-1-Pad19)") (class "Default")
      (node (ref "X2") (pin "19") (pinfunction "1_19") (pintype "passive"))
    )
    (net (code "267") (name "unconnected-(X2L-1-Pad2)") (class "Default")
      (node (ref "X2") (pin "2") (pinfunction "1_2") (pintype "passive"))
    )
    (net (code "268") (name "unconnected-(X2M-1-Pad20)") (class "Default")
      (node (ref "X2") (pin "20") (pinfunction "1_20") (pintype "passive"))
    )
    (net (code "269") (name "unconnected-(X2N-1-Pad21)") (class "Default")
      (node (ref "X2") (pin "21") (pinfunction "1_21") (pintype "passive"))
    )
    (net (code "270") (name "unconnected-(X2O-1-Pad22)") (class "Default")
      (node (ref "X2") (pin "22") (pinfunction "1_22") (pintype "passive"))
    )
    (net (code "271") (name "unconnected-(X2P-1-Pad23)") (class "Default")
      (node (ref "X2") (pin "23") (pinfunction "1_23") (pintype "passive"))
    )
    (net (code "272") (name "unconnected-(X2Q-1-Pad24)") (class "Default")
      (node (ref "X2") (pin "24") (pinfunction "1_24") (pintype "passive"))
    )
    (net (code "273") (name "unconnected-(X2R-1-Pad25)") (class "Default")
      (node (ref "X2") (pin "25") (pinfunction "1_25") (pintype "passive"))
    )
    (net (code "274") (name "unconnected-(X2S-1-Pad26)") (class "Default")
      (node (ref "X2") (pin "26") (pinfunction "1_26") (pintype "passive"))
    )
    (net (code "275") (name "unconnected-(X2T-1-Pad27)") (class "Default")
      (node (ref "X2") (pin "27") (pinfunction "1_27") (pintype "passive"))
    )
    (net (code "276") (name "unconnected-(X2U-1-Pad28)") (class "Default")
      (node (ref "X2") (pin "28") (pinfunction "1_28") (pintype "passive"))
    )
    (net (code "277") (name "unconnected-(X2V-1-Pad29)") (class "Default")
      (node (ref "X2") (pin "29") (pinfunction "1_29") (pintype "passive"))
    )
    (net (code "278") (name "unconnected-(X2W-1-Pad3)") (class "Default")
      (node (ref "X2") (pin "3") (pinfunction "1_3") (pintype "passive"))
    )
    (net (code "279") (name "unconnected-(X2X-1-Pad30)") (class "Default")
      (node (ref "X2") (pin "30") (pinfunction "1_30") (pintype "passive"))
    )
    (net (code "280") (name "unconnected-(X2Y-1-Pad31)") (class "Default")
      (node (ref "X2") (pin "31") (pinfunction "1_31") (pintype "passive"))
    )
    (net (code "281") (name "unconnected-(X2Z-1-Pad32)") (class "Default")
      (node (ref "X2") (pin "32") (pinfunction "1_32") (pintype "passive"))
    )
  )
)
